# Bipolar_Stepper_Motor_Controller_RevA.net
KiCad netlist of a schematic drawn in EAGLE
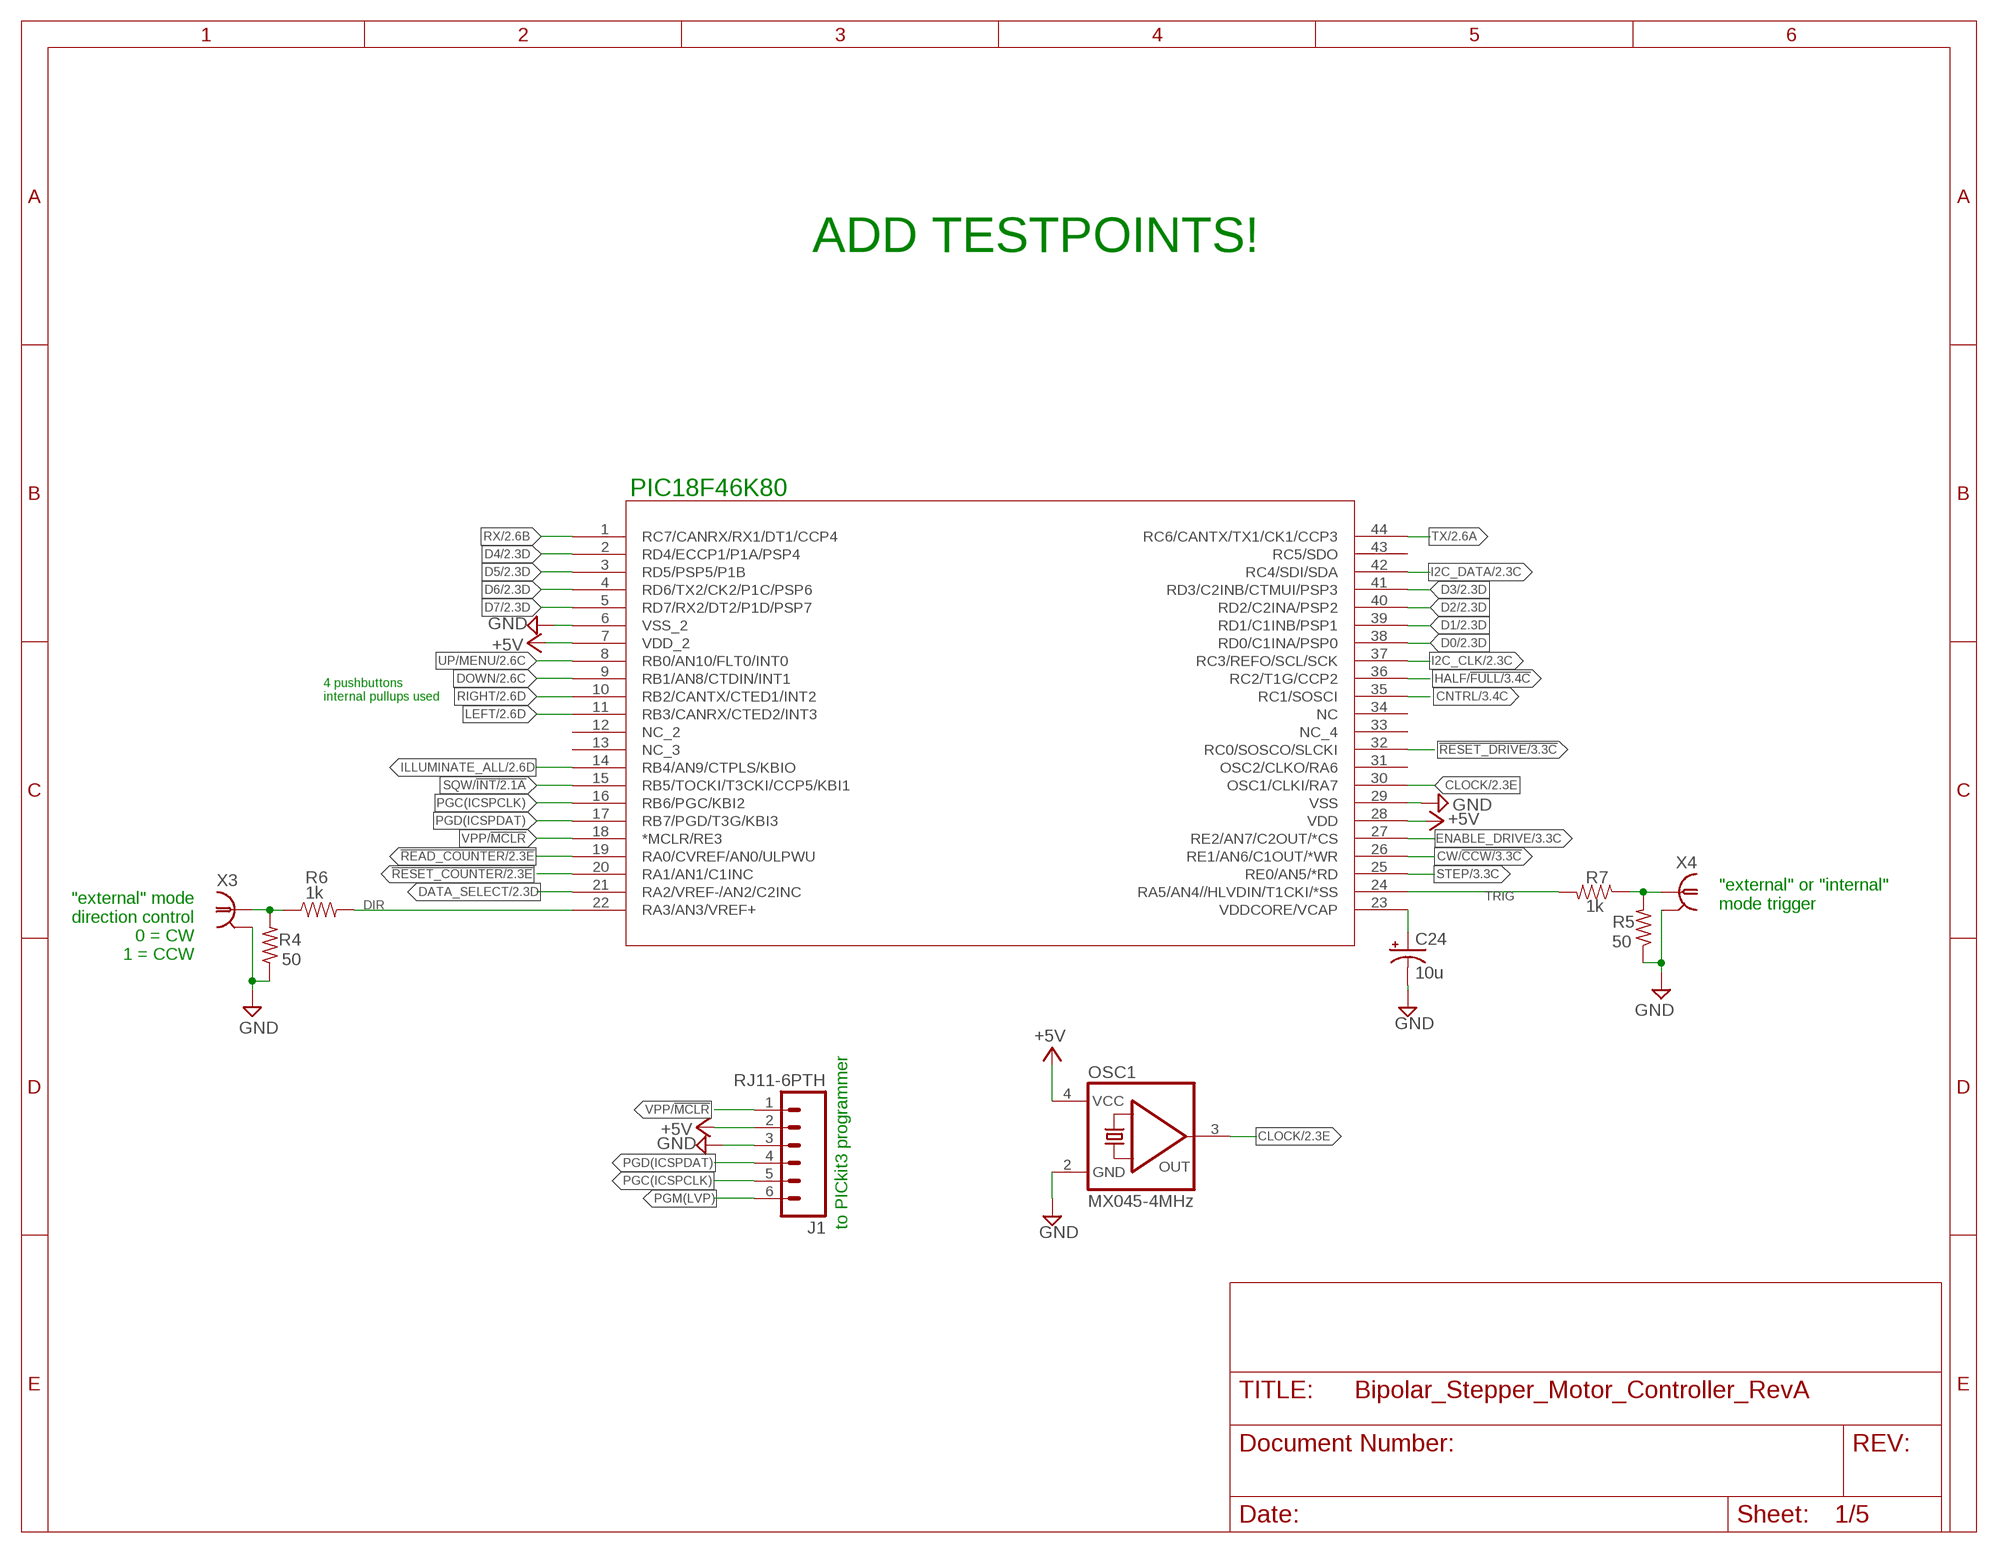
[diagram p0: schematic, sheet 1]
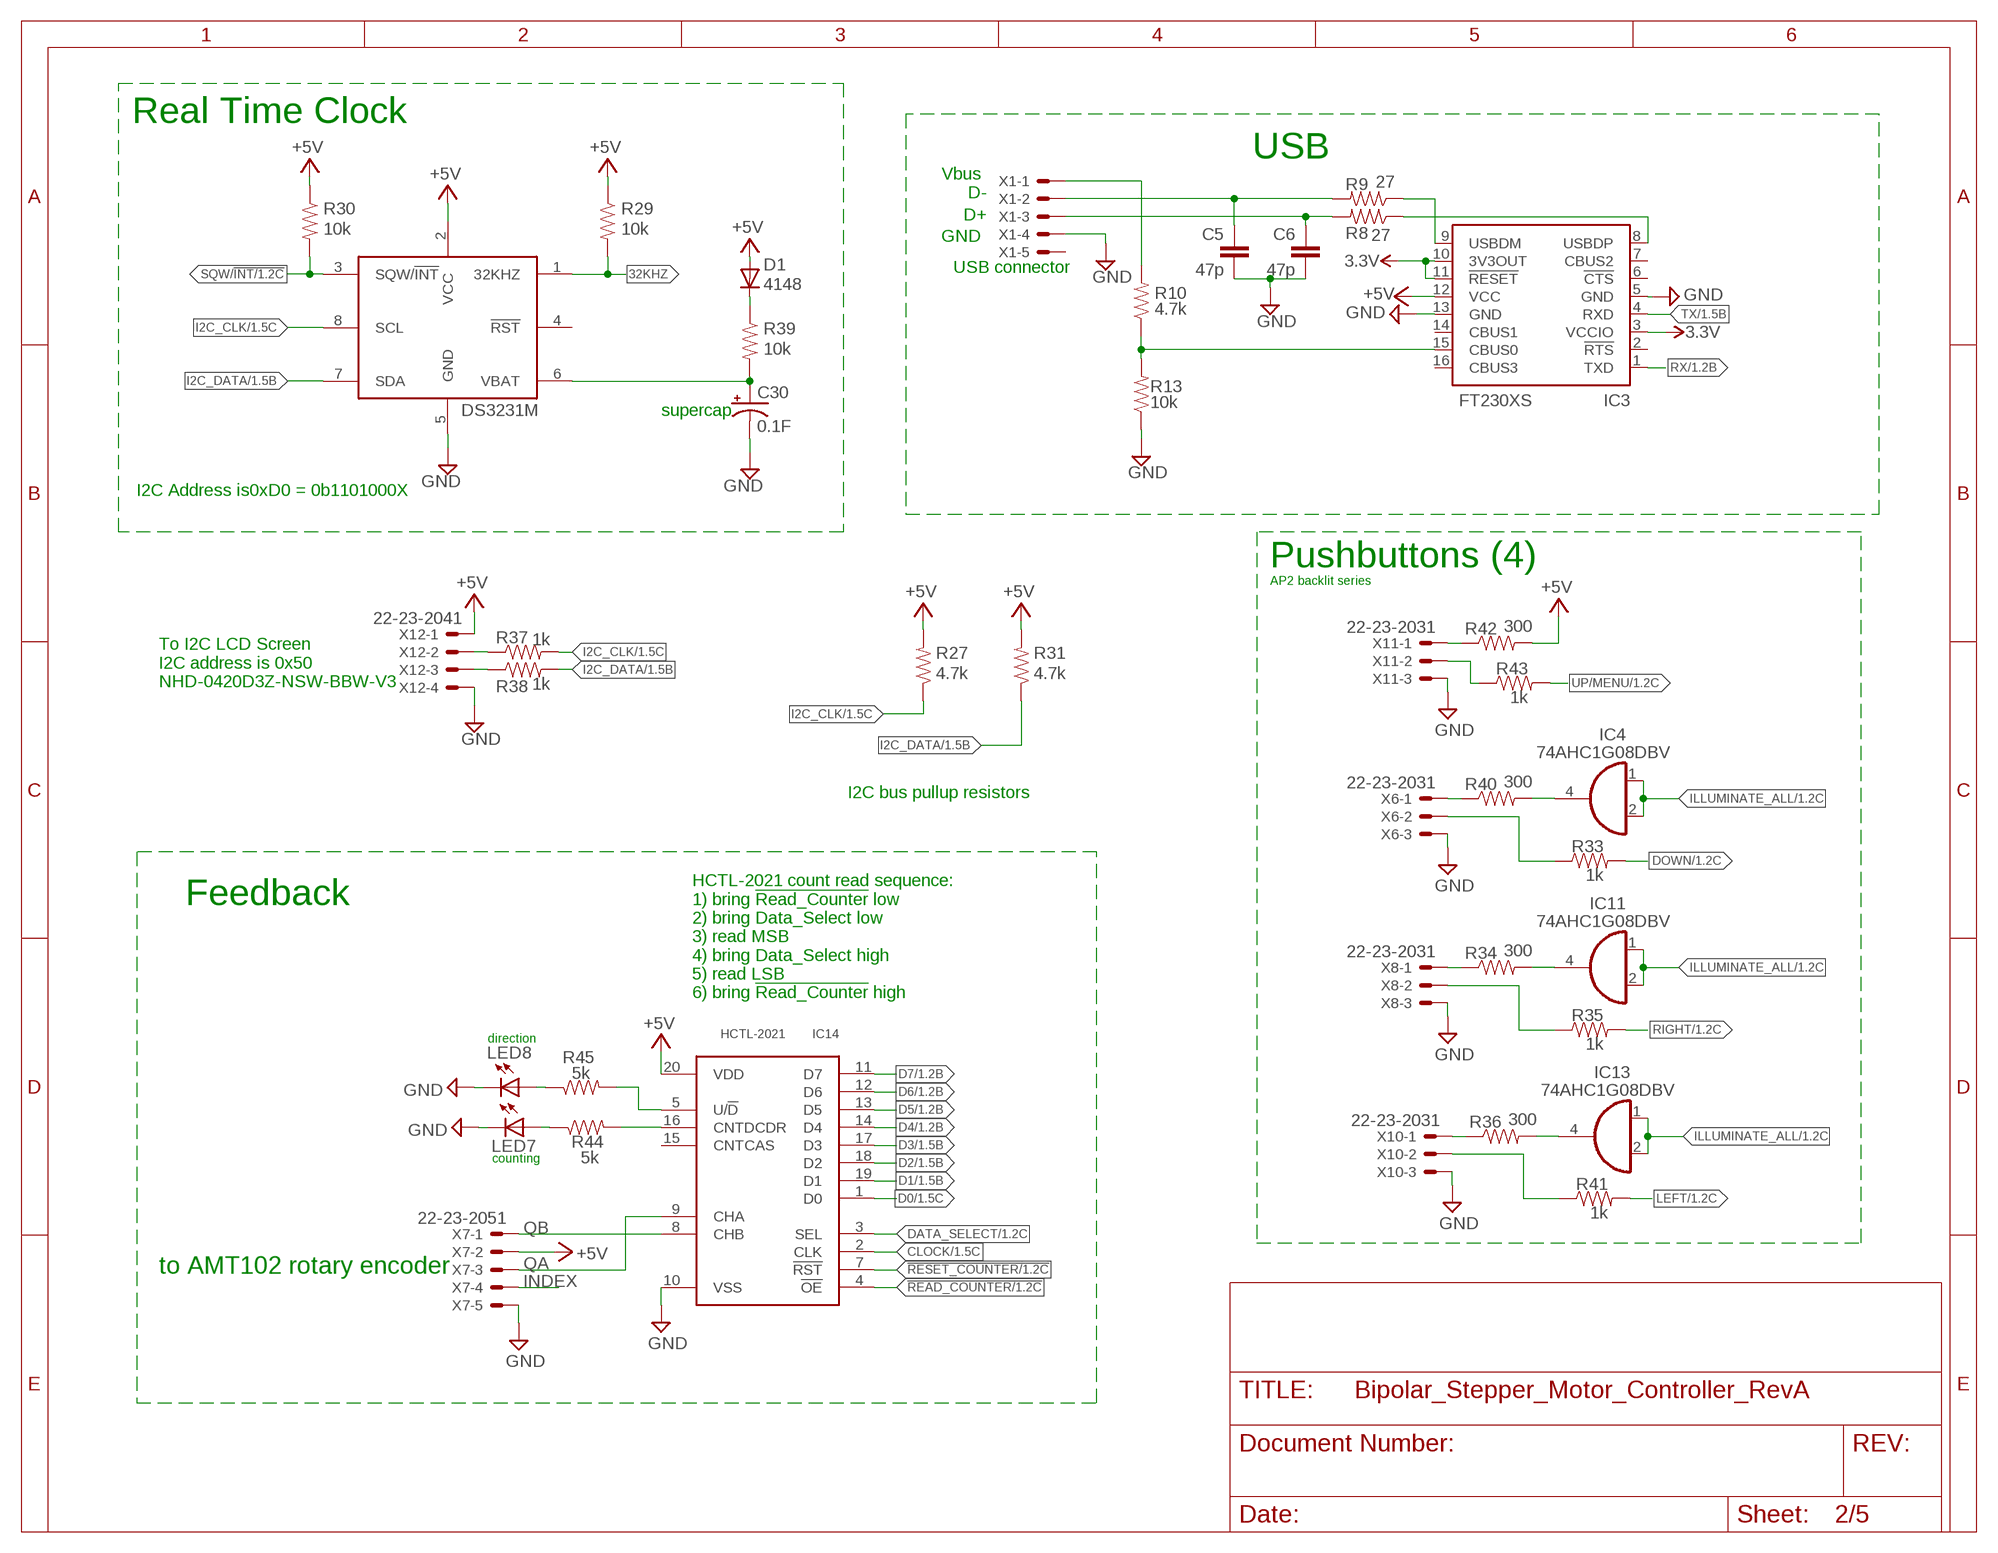
[diagram p1: schematic, sheet 2]
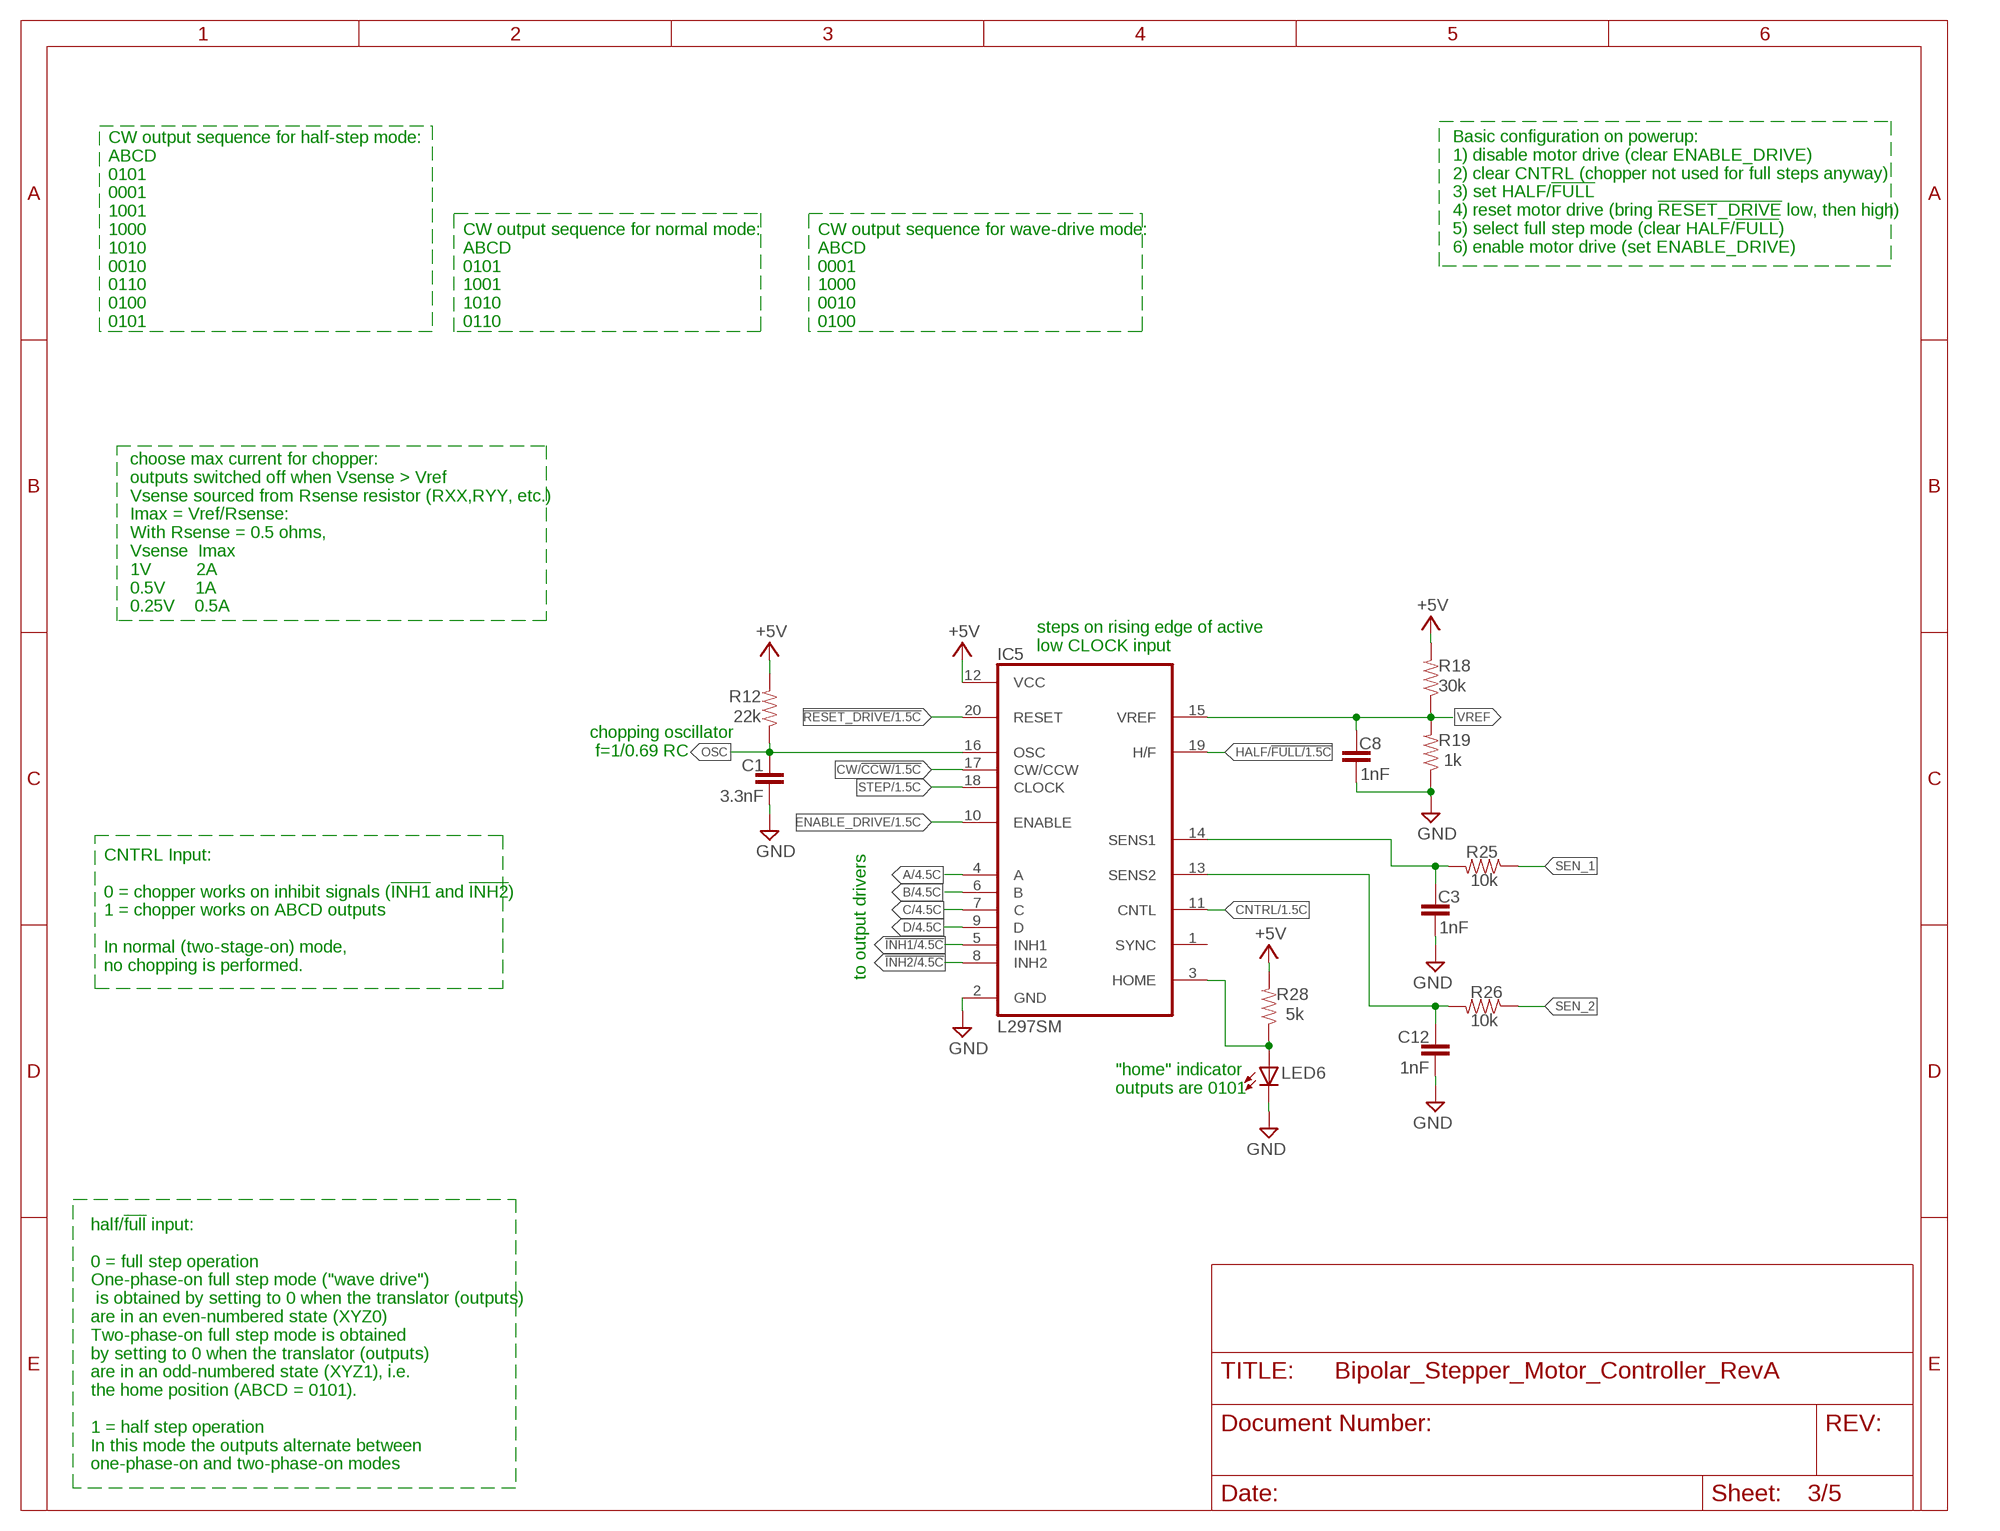
[diagram p2: schematic, sheet 3]
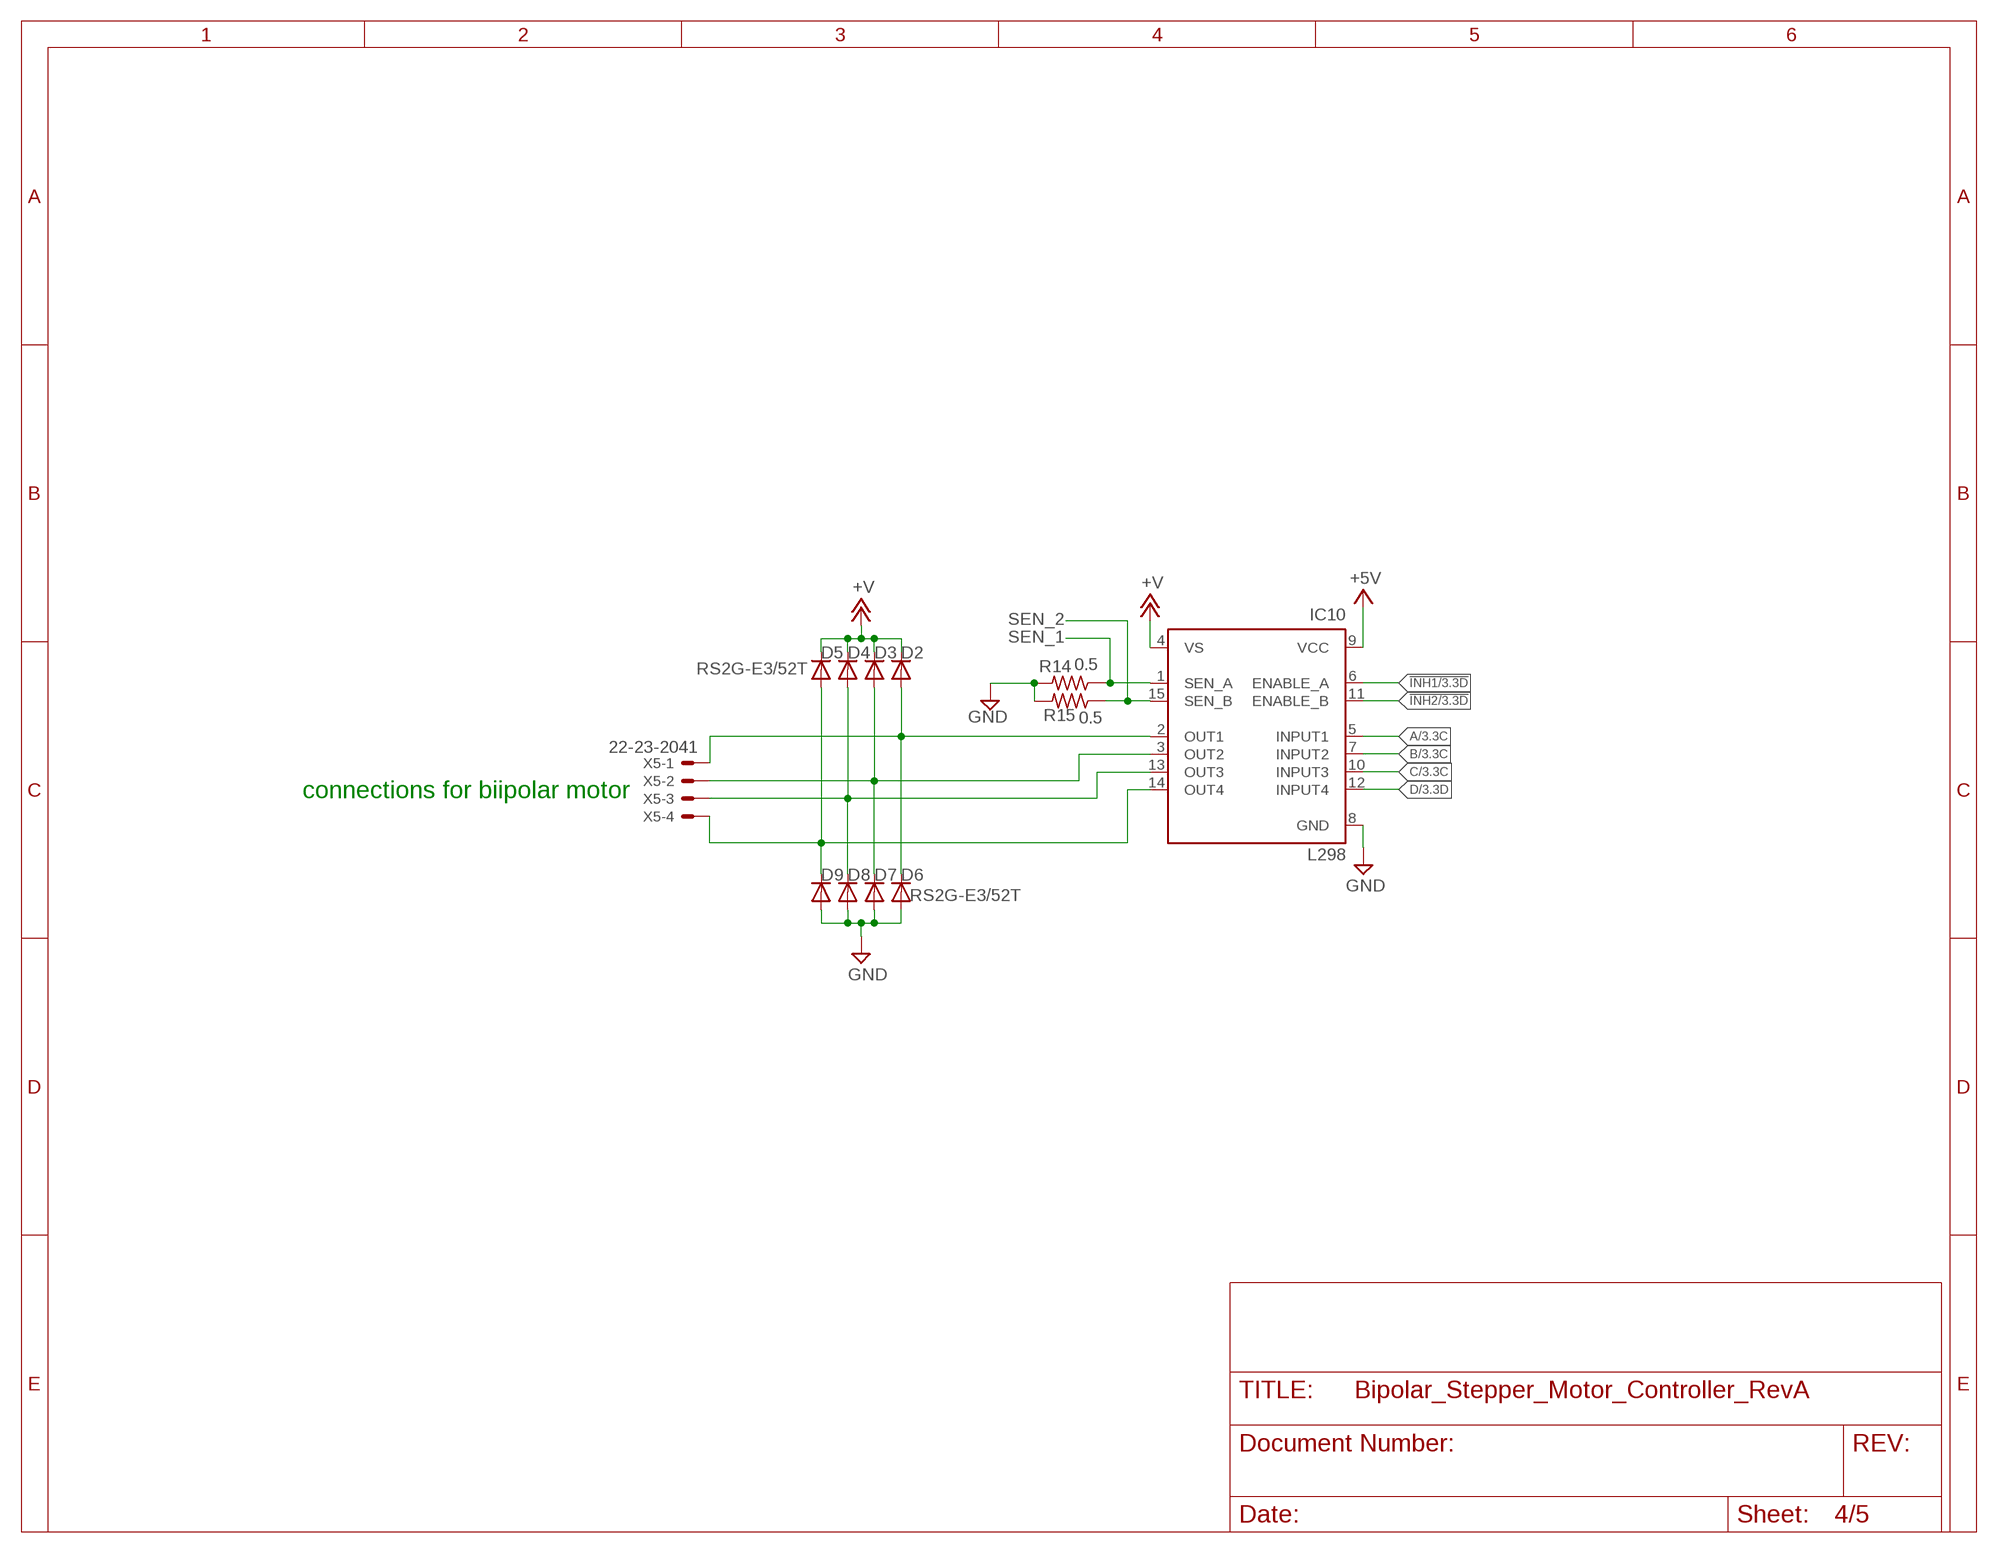
[diagram p3: schematic, sheet 4]
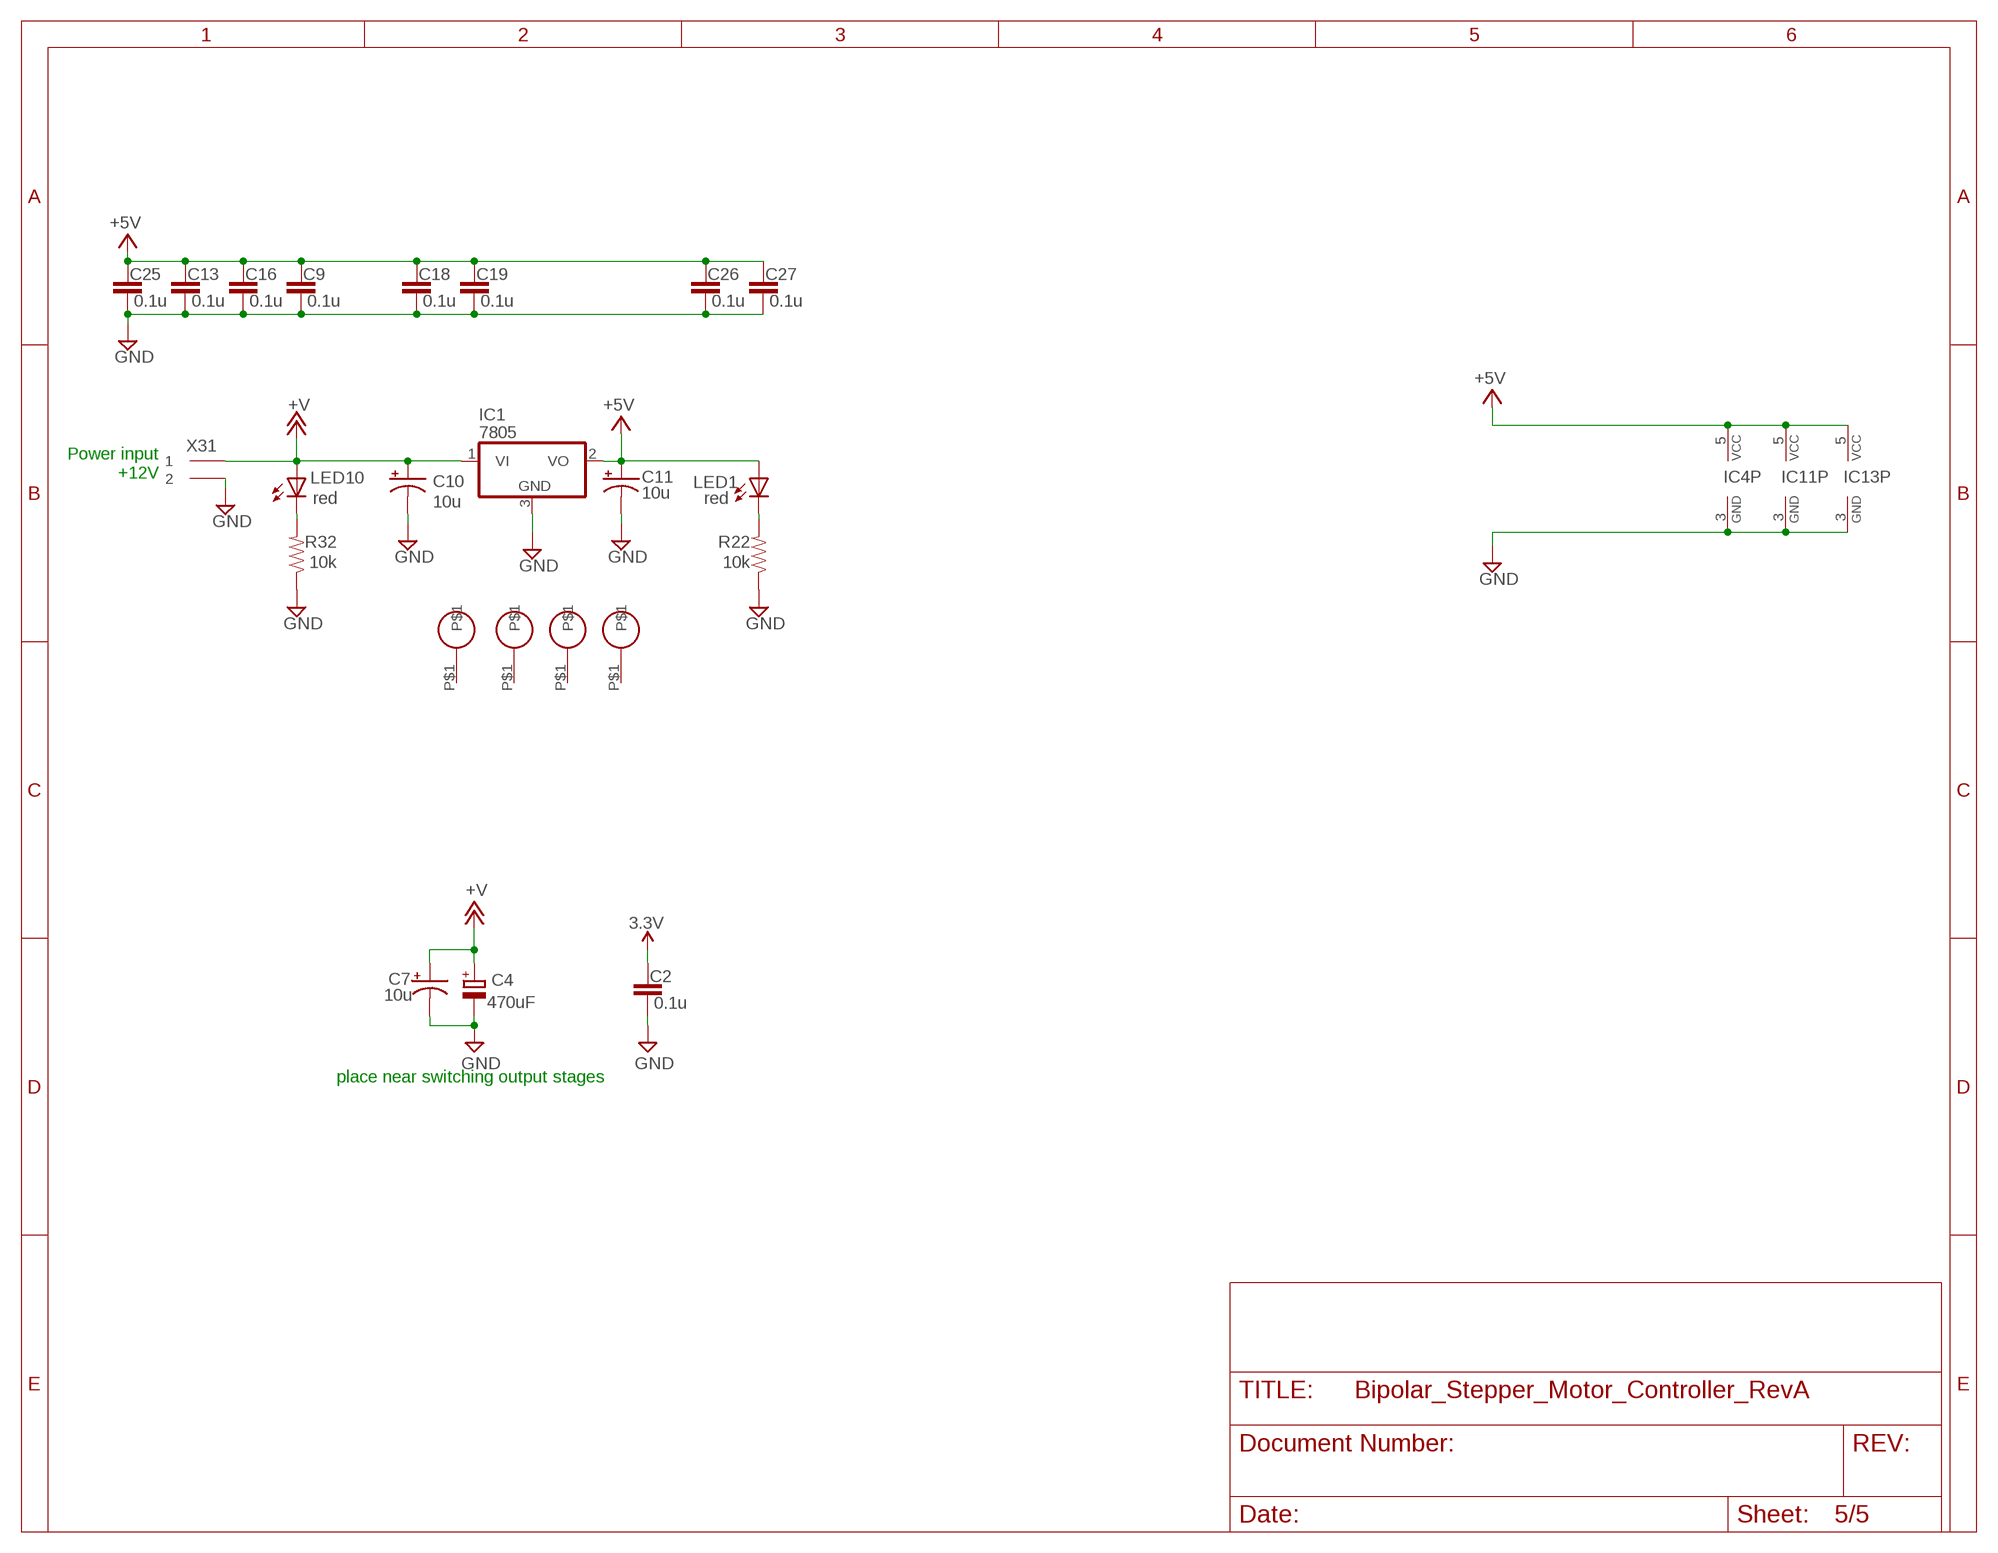
[diagram p4: schematic, sheet 5]

(export (version "E")
  (design (tool "Eeschema 10.0.6"))
  (components
    (comp (ref "C24")
      (value "10u")
      (footprint "eagle-import:EIA3216")
      (libsource (lib "eagle-import") (part "CAP_POL1206"))
    )
    (comp (ref "IC12")
      (value "PIC18F46K80")
      (footprint "eagle-import:TQFP44_MC")
      (libsource (lib "eagle-import") (part "PIC18F46K80"))
    )
    (comp (ref "J1")
      (value "RJ11-6PTH")
      (footprint "eagle-import:RJ11-6")
      (libsource (lib "eagle-import") (part "RJ11-6PTH"))
    )
    (comp (ref "OSC1")
      (value "MX045-4MHz")
      (footprint "eagle-import:DIL08-4")
      (libsource (lib "eagle-import") (part "SG531"))
    )
    (comp (ref "R4")
      (value "50")
      (footprint "eagle-import:R2512")
      (libsource (lib "eagle-import") (part "R-US_R2512"))
    )
    (comp (ref "R5")
      (value "50")
      (footprint "eagle-import:R2512")
      (libsource (lib "eagle-import") (part "R-US_R2512"))
    )
    (comp (ref "R6")
      (value "1k")
      (footprint "eagle-import:0805")
      (libsource (lib "eagle-import") (part "RESISTOR"))
    )
    (comp (ref "R7")
      (value "1k")
      (footprint "eagle-import:0805")
      (libsource (lib "eagle-import") (part "RESISTOR"))
    )
    (comp (ref "X3")
      (value "1-227161-0")
      (footprint "eagle-import:AMP_227161")
      (fields (field (name "MF") "TYCO ELECTRONICS") (field (name "MPN") "1-227161"))
      (libsource (lib "eagle-import") (part "?2271611--0"))
    )
    (comp (ref "X4")
      (value "1-227161-0")
      (footprint "eagle-import:AMP_227161")
      (fields (field (name "MF") "TYCO ELECTRONICS") (field (name "MPN") "1-227161"))
      (libsource (lib "eagle-import") (part "?2271611--0"))
    )
    (comp (ref "D2")
      (value "RS2G-E3/52T")
      (footprint "eagle-import:DO214AA")
      (libsource (lib "eagle-import") (part "DIODE-DO214AA"))
    )
    (comp (ref "D3")
      (value "RS2G-E3/52T")
      (footprint "eagle-import:DO214AA")
      (libsource (lib "eagle-import") (part "DIODE-DO214AA"))
    )
    (comp (ref "D4")
      (value "RS2G-E3/52T")
      (footprint "eagle-import:DO214AA")
      (libsource (lib "eagle-import") (part "DIODE-DO214AA"))
    )
    (comp (ref "D5")
      (value "RS2G-E3/52T")
      (footprint "eagle-import:DO214AA")
      (libsource (lib "eagle-import") (part "DIODE-DO214AA"))
    )
    (comp (ref "D6")
      (value "RS2G-E3/52T")
      (footprint "eagle-import:DO214AA")
      (libsource (lib "eagle-import") (part "DIODE-DO214AA"))
    )
    (comp (ref "D7")
      (value "RS2G-E3/52T")
      (footprint "eagle-import:DO214AA")
      (libsource (lib "eagle-import") (part "DIODE-DO214AA"))
    )
    (comp (ref "D8")
      (value "RS2G-E3/52T")
      (footprint "eagle-import:DO214AA")
      (libsource (lib "eagle-import") (part "DIODE-DO214AA"))
    )
    (comp (ref "D9")
      (value "RS2G-E3/52T")
      (footprint "eagle-import:DO214AA")
      (libsource (lib "eagle-import") (part "DIODE-DO214AA"))
    )
    (comp (ref "IC10")
      (value "L298")
      (footprint "eagle-import:MULTIWATT-15")
      (fields (field (name "MPN") "L298N"))
      (libsource (lib "eagle-import") (part "L298"))
    )
    (comp (ref "R14")
      (value "0.5")
      (footprint "eagle-import:R2512")
      (libsource (lib "eagle-import") (part "resistor_R-US_R2512"))
    )
    (comp (ref "R15")
      (value "0.5")
      (footprint "eagle-import:R2512")
      (libsource (lib "eagle-import") (part "resistor_R-US_R2512"))
    )
    (comp (ref "X5")
      (value "22-23-2041")
      (footprint "eagle-import:22-23-2041")
      (fields (field (name "MF") "MOLEX"))
      (libsource (lib "eagle-import") (part "22-23-2041"))
    )
    (comp (ref "C1")
      (value "3.3nF")
      (footprint "eagle-import:0603-CAP")
      (libsource (lib "eagle-import") (part "CAP0603-CAP"))
    )
    (comp (ref "C3")
      (value "1nF")
      (footprint "eagle-import:0603-CAP")
      (libsource (lib "eagle-import") (part "CAP0603-CAP"))
    )
    (comp (ref "C8")
      (value "1nF")
      (footprint "eagle-import:0603-CAP")
      (libsource (lib "eagle-import") (part "CAP0603-CAP"))
    )
    (comp (ref "C12")
      (value "1nF")
      (footprint "eagle-import:0603-CAP")
      (libsource (lib "eagle-import") (part "CAP0603-CAP"))
    )
    (comp (ref "IC5")
      (value "L297SM")
      (footprint "eagle-import:SO20")
      (libsource (lib "eagle-import") (part "L297SM"))
    )
    (comp (ref "LED6")
      (value "red")
      (footprint "eagle-import:CHIPLED_0603")
      (libsource (lib "eagle-import") (part "LEDCHIPLED_0603"))
    )
    (comp (ref "R12")
      (value "22k")
      (footprint "eagle-import:0603-RES")
      (libsource (lib "eagle-import") (part "RESISTOR0603-RES"))
    )
    (comp (ref "R18")
      (value "30k")
      (footprint "eagle-import:0603-RES")
      (libsource (lib "eagle-import") (part "RESISTOR0603-RES"))
    )
    (comp (ref "R19")
      (value "1k")
      (footprint "eagle-import:0603-RES")
      (libsource (lib "eagle-import") (part "RESISTOR0603-RES"))
    )
    (comp (ref "R25")
      (value "10k")
      (footprint "eagle-import:0603-RES")
      (libsource (lib "eagle-import") (part "RESISTOR0603-RES"))
    )
    (comp (ref "R26")
      (value "10k")
      (footprint "eagle-import:0603-RES")
      (libsource (lib "eagle-import") (part "RESISTOR0603-RES"))
    )
    (comp (ref "R28")
      (value "5k")
      (footprint "eagle-import:0603-RES")
      (libsource (lib "eagle-import") (part "RESISTOR0603-RES"))
    )
    (comp (ref "C5")
      (value "47p")
      (footprint "eagle-import:0805")
      (libsource (lib "eagle-import") (part "CAP0805"))
    )
    (comp (ref "C6")
      (value "47p")
      (footprint "eagle-import:0805")
      (libsource (lib "eagle-import") (part "CAP0805"))
    )
    (comp (ref "C30")
      (value "0.1F")
      (footprint "eagle-import:P128-60")
      (libsource (lib "eagle-import") (part "CPOL-USP128-60"))
    )
    (comp (ref "D1")
      (value "4148")
      (footprint "eagle-import:SOT23-3")
      (libsource (lib "eagle-import") (part "DIODESOT23"))
    )
    (comp (ref "IC3")
      (value "FT230XS")
      (footprint "eagle-import:SSOP16")
      (libsource (lib "eagle-import") (part "FT230XS"))
    )
    (comp (ref "IC4")
      (value "74AHC1G08DBV")
      (footprint "eagle-import:SOT23-5")
      (libsource (lib "eagle-import") (part "741G08DBVAHC"))
    )
    (comp (ref "IC6")
      (value "DS3231M")
      (footprint "eagle-import:8-SOIC")
      (libsource (lib "eagle-import") (part "DS3231M"))
    )
    (comp (ref "IC11")
      (value "74AHC1G08DBV")
      (footprint "eagle-import:SOT23-5")
      (libsource (lib "eagle-import") (part "741G08DBVAHC"))
    )
    (comp (ref "IC13")
      (value "74AHC1G08DBV")
      (footprint "eagle-import:SOT23-5")
      (libsource (lib "eagle-import") (part "741G08DBVAHC"))
    )
    (comp (ref "IC14")
      (value "HCTL-2021")
      (footprint "eagle-import:PLCC20")
      (libsource (lib "eagle-import") (part "HCTL-2021"))
    )
    (comp (ref "LED7")
      (value "red")
      (footprint "eagle-import:CHIPLED_0603")
      (libsource (lib "eagle-import") (part "LEDCHIPLED_0603"))
    )
    (comp (ref "LED8")
      (value "red")
      (footprint "eagle-import:CHIPLED_0603")
      (libsource (lib "eagle-import") (part "LEDCHIPLED_0603"))
    )
    (comp (ref "R8")
      (value "27")
      (footprint "eagle-import:0805")
      (libsource (lib "eagle-import") (part "RESISTOR"))
    )
    (comp (ref "R9")
      (value "27")
      (footprint "eagle-import:0805")
      (libsource (lib "eagle-import") (part "RESISTOR"))
    )
    (comp (ref "R10")
      (value "4.7k")
      (footprint "eagle-import:0805")
      (libsource (lib "eagle-import") (part "RESISTOR"))
    )
    (comp (ref "R13")
      (value "10k")
      (footprint "eagle-import:0805")
      (libsource (lib "eagle-import") (part "RESISTOR"))
    )
    (comp (ref "R27")
      (value "4.7k")
      (footprint "eagle-import:0603-RES")
      (libsource (lib "eagle-import") (part "RESISTOR0603-RES"))
    )
    (comp (ref "R29")
      (value "10k")
      (footprint "eagle-import:0603-RES")
      (libsource (lib "eagle-import") (part "RESISTOR0603-RES"))
    )
    (comp (ref "R30")
      (value "10k")
      (footprint "eagle-import:0603-RES")
      (libsource (lib "eagle-import") (part "RESISTOR0603-RES"))
    )
    (comp (ref "R31")
      (value "4.7k")
      (footprint "eagle-import:0603-RES")
      (libsource (lib "eagle-import") (part "RESISTOR0603-RES"))
    )
    (comp (ref "R33")
      (value "1k")
      (footprint "eagle-import:0805")
      (libsource (lib "eagle-import") (part "RESISTOR"))
    )
    (comp (ref "R34")
      (value "300")
      (footprint "eagle-import:0805")
      (libsource (lib "eagle-import") (part "RESISTOR"))
    )
    (comp (ref "R35")
      (value "1k")
      (footprint "eagle-import:0805")
      (libsource (lib "eagle-import") (part "RESISTOR"))
    )
    (comp (ref "R36")
      (value "300")
      (footprint "eagle-import:0805")
      (libsource (lib "eagle-import") (part "RESISTOR"))
    )
    (comp (ref "R37")
      (value "1k")
      (footprint "eagle-import:0805")
      (libsource (lib "eagle-import") (part "RESISTOR"))
    )
    (comp (ref "R38")
      (value "1k")
      (footprint "eagle-import:0805")
      (libsource (lib "eagle-import") (part "RESISTOR"))
    )
    (comp (ref "R39")
      (value "10k")
      (footprint "eagle-import:0603-RES")
      (libsource (lib "eagle-import") (part "RESISTOR0603-RES"))
    )
    (comp (ref "R40")
      (value "300")
      (footprint "eagle-import:0805")
      (libsource (lib "eagle-import") (part "RESISTOR"))
    )
    (comp (ref "R41")
      (value "1k")
      (footprint "eagle-import:0805")
      (libsource (lib "eagle-import") (part "RESISTOR"))
    )
    (comp (ref "R42")
      (value "300")
      (footprint "eagle-import:0805")
      (libsource (lib "eagle-import") (part "RESISTOR"))
    )
    (comp (ref "R43")
      (value "1k")
      (footprint "eagle-import:0805")
      (libsource (lib "eagle-import") (part "RESISTOR"))
    )
    (comp (ref "R44")
      (value "5k")
      (footprint "eagle-import:0603-RES")
      (libsource (lib "eagle-import") (part "RESISTOR0603-RES"))
    )
    (comp (ref "R45")
      (value "5k")
      (footprint "eagle-import:0603-RES")
      (libsource (lib "eagle-import") (part "RESISTOR0603-RES"))
    )
    (comp (ref "X1")
      (value "22-23-2051")
      (footprint "eagle-import:22-23-2051")
      (fields (field (name "MF") "MOLEX"))
      (libsource (lib "eagle-import") (part "22-23-2051"))
    )
    (comp (ref "X6")
      (value "22-23-2031")
      (footprint "eagle-import:22-23-2031")
      (fields (field (name "MF") "MOLEX"))
      (libsource (lib "eagle-import") (part "22-23-2031"))
    )
    (comp (ref "X7")
      (value "22-23-2051")
      (footprint "eagle-import:22-23-2051")
      (fields (field (name "MF") "MOLEX"))
      (libsource (lib "eagle-import") (part "22-23-2051"))
    )
    (comp (ref "X8")
      (value "22-23-2031")
      (footprint "eagle-import:22-23-2031")
      (fields (field (name "MF") "MOLEX"))
      (libsource (lib "eagle-import") (part "22-23-2031"))
    )
    (comp (ref "X10")
      (value "22-23-2031")
      (footprint "eagle-import:22-23-2031")
      (fields (field (name "MF") "MOLEX"))
      (libsource (lib "eagle-import") (part "22-23-2031"))
    )
    (comp (ref "X11")
      (value "22-23-2031")
      (footprint "eagle-import:22-23-2031")
      (fields (field (name "MF") "MOLEX"))
      (libsource (lib "eagle-import") (part "22-23-2031"))
    )
    (comp (ref "X12")
      (value "22-23-2041")
      (footprint "eagle-import:22-23-2041")
      (fields (field (name "MF") "MOLEX"))
      (libsource (lib "eagle-import") (part "22-23-2041"))
    )
    (comp (ref "C2")
      (value "0.1u")
      (footprint "eagle-import:0603-CAP")
      (libsource (lib "eagle-import") (part "CAP0603-CAP"))
    )
    (comp (ref "C4")
      (value "470uF")
      (footprint "eagle-import:SANYO-OSCON_SMD_F8")
      (libsource (lib "eagle-import") (part "CPOL-EUSANYO_SMD_F8"))
    )
    (comp (ref "C7")
      (value "10u")
      (footprint "eagle-import:EIA3216")
      (libsource (lib "eagle-import") (part "CAP_POL1206"))
    )
    (comp (ref "C9")
      (value "0.1u")
      (footprint "eagle-import:0603-CAP")
      (libsource (lib "eagle-import") (part "CAP0603-CAP"))
    )
    (comp (ref "C10")
      (value "10u")
      (footprint "eagle-import:EIA3216")
      (libsource (lib "eagle-import") (part "CAP_POL1206"))
    )
    (comp (ref "C11")
      (value "10u")
      (footprint "eagle-import:EIA3216")
      (libsource (lib "eagle-import") (part "CAP_POL1206"))
    )
    (comp (ref "C13")
      (value "0.1u")
      (footprint "eagle-import:0603-CAP")
      (libsource (lib "eagle-import") (part "CAP0603-CAP"))
    )
    (comp (ref "C16")
      (value "0.1u")
      (footprint "eagle-import:0603-CAP")
      (libsource (lib "eagle-import") (part "CAP0603-CAP"))
    )
    (comp (ref "C18")
      (value "0.1u")
      (footprint "eagle-import:0603-CAP")
      (libsource (lib "eagle-import") (part "CAP0603-CAP"))
    )
    (comp (ref "C19")
      (value "0.1u")
      (footprint "eagle-import:0603-CAP")
      (libsource (lib "eagle-import") (part "CAP0603-CAP"))
    )
    (comp (ref "C25")
      (value "0.1u")
      (footprint "eagle-import:0603-CAP")
      (libsource (lib "eagle-import") (part "CAP0603-CAP"))
    )
    (comp (ref "C26")
      (value "0.1u")
      (footprint "eagle-import:0603-CAP")
      (libsource (lib "eagle-import") (part "CAP0603-CAP"))
    )
    (comp (ref "C27")
      (value "0.1u")
      (footprint "eagle-import:0603-CAP")
      (libsource (lib "eagle-import") (part "CAP0603-CAP"))
    )
    (comp (ref "IC1")
      (value "7805")
      (footprint "eagle-import:TO252")
      (libsource (lib "eagle-import") (part "78DT24"))
    )
    (comp (ref "LED1")
      (value "red")
      (footprint "eagle-import:CHIPLED_0805")
      (libsource (lib "eagle-import") (part "LEDCHIPLED_0805"))
    )
    (comp (ref "LED10")
      (value "red")
      (footprint "eagle-import:CHIPLED_0805")
      (libsource (lib "eagle-import") (part "LEDCHIPLED_0805"))
    )
    (comp (ref "R22")
      (value "10k")
      (footprint "eagle-import:0805")
      (libsource (lib "eagle-import") (part "RESISTOR"))
    )
    (comp (ref "R32")
      (value "10k")
      (footprint "eagle-import:0805")
      (libsource (lib "eagle-import") (part "RESISTOR"))
    )
    (comp (ref "U$1")
      (value "2-56")
      (footprint "eagle-import:2-56")
      (libsource (lib "eagle-import") (part "2-56"))
    )
    (comp (ref "U$2")
      (value "2-56")
      (footprint "eagle-import:2-56")
      (libsource (lib "eagle-import") (part "2-56"))
    )
    (comp (ref "U$3")
      (value "2-56")
      (footprint "eagle-import:2-56")
      (libsource (lib "eagle-import") (part "2-56"))
    )
    (comp (ref "U$4")
      (value "2-56")
      (footprint "eagle-import:2-56")
      (libsource (lib "eagle-import") (part "2-56"))
    )
    (comp (ref "X31")
      (value "SL_70543_2")
      (footprint "eagle-import:SL_70543_2")
      (libsource (lib "eagle-import") (part "SL_70543_2"))
    )
  )
  (nets
    (net (code "1") (name "+5V") (class "Default")
      (node (ref "C11") (pin "A") (pinfunction "+_A") (pintype "passive"))
      (node (ref "C13") (pin "1") (pinfunction "1_1") (pintype "passive"))
      (node (ref "C16") (pin "1") (pinfunction "1_1") (pintype "passive"))
      (node (ref "C18") (pin "1") (pinfunction "1_1") (pintype "passive"))
      (node (ref "C19") (pin "1") (pinfunction "1_1") (pintype "passive"))
      (node (ref "C25") (pin "1") (pinfunction "1_1") (pintype "passive"))
      (node (ref "C26") (pin "1") (pinfunction "1_1") (pintype "passive"))
      (node (ref "C27") (pin "1") (pinfunction "1_1") (pintype "passive"))
      (node (ref "C9") (pin "1") (pinfunction "1_1") (pintype "passive"))
      (node (ref "D1") (pin "1") (pinfunction "A_1") (pintype "passive"))
      (node (ref "IC1") (pin "2") (pinfunction "VO_2") (pintype "passive"))
      (node (ref "IC10") (pin "9") (pinfunction "VCC_9") (pintype "power_in"))
      (node (ref "IC11") (pin "5") (pinfunction "VCC_5") (pintype "power_in"))
      (node (ref "IC12") (pin "28") (pinfunction "VDD_28") (pintype "passive"))
      (node (ref "IC12") (pin "7") (pinfunction "VDD_2_7") (pintype "passive"))
      (node (ref "IC13") (pin "5") (pinfunction "VCC_5") (pintype "power_in"))
      (node (ref "IC14") (pin "20") (pinfunction "VDD_20") (pintype "bidirectional"))
      (node (ref "IC3") (pin "12") (pinfunction "VCC_12") (pintype "power_in"))
      (node (ref "IC4") (pin "5") (pinfunction "VCC_5") (pintype "power_in"))
      (node (ref "IC5") (pin "12") (pinfunction "VCC_12") (pintype "power_in"))
      (node (ref "IC6") (pin "2") (pinfunction "VCC_2") (pintype "bidirectional"))
      (node (ref "J1") (pin "2") (pinfunction "2_2") (pintype "passive"))
      (node (ref "LED1") (pin "A") (pinfunction "A_A") (pintype "passive"))
      (node (ref "OSC1") (pin "4") (pinfunction "VCC_4") (pintype "power_in"))
      (node (ref "R12") (pin "2") (pinfunction "2_2") (pintype "passive"))
      (node (ref "R18") (pin "2") (pinfunction "2_2") (pintype "passive"))
      (node (ref "R27") (pin "2") (pinfunction "2_2") (pintype "passive"))
      (node (ref "R28") (pin "2") (pinfunction "2_2") (pintype "passive"))
      (node (ref "R29") (pin "1") (pinfunction "1_1") (pintype "passive"))
      (node (ref "R30") (pin "1") (pinfunction "1_1") (pintype "passive"))
      (node (ref "R31") (pin "2") (pinfunction "2_2") (pintype "passive"))
      (node (ref "R42") (pin "2") (pinfunction "2_2") (pintype "passive"))
      (node (ref "X12") (pin "1") (pinfunction "S_1") (pintype "passive"))
      (node (ref "X7") (pin "2") (pinfunction "S_2") (pintype "passive"))
    )
    (net (code "2") (name "+V") (class "Default")
      (node (ref "C10") (pin "A") (pinfunction "+_A") (pintype "passive"))
      (node (ref "C4") (pin "+") (pinfunction "+_+") (pintype "passive"))
      (node (ref "C7") (pin "A") (pinfunction "+_A") (pintype "passive"))
      (node (ref "D2") (pin "C") (pinfunction "C_C") (pintype "passive"))
      (node (ref "D3") (pin "C") (pinfunction "C_C") (pintype "passive"))
      (node (ref "D4") (pin "C") (pinfunction "C_C") (pintype "passive"))
      (node (ref "D5") (pin "C") (pinfunction "C_C") (pintype "passive"))
      (node (ref "IC1") (pin "1") (pinfunction "VI_1") (pintype "input"))
      (node (ref "IC10") (pin "4") (pinfunction "VS_4") (pintype "power_in"))
      (node (ref "LED10") (pin "A") (pinfunction "A_A") (pintype "passive"))
      (node (ref "X31") (pin "P$1") (pinfunction "1_P$1") (pintype "bidirectional"))
    )
    (net (code "3") (name "3.3V") (class "Default")
      (node (ref "C2") (pin "1") (pinfunction "1_1") (pintype "passive"))
      (node (ref "IC3") (pin "10") (pinfunction "3V3OUT_10") (pintype "output"))
      (node (ref "IC3") (pin "11") (pinfunction "~{RESET}_11") (pintype "input"))
      (node (ref "IC3") (pin "3") (pinfunction "VCCIO_3") (pintype "power_in"))
    )
    (net (code "4") (name "32KHZ") (class "Default")
      (node (ref "IC6") (pin "1") (pinfunction "32KHZ_1") (pintype "bidirectional"))
      (node (ref "R29") (pin "2") (pinfunction "2_2") (pintype "passive"))
    )
    (net (code "5") (name "A") (class "Default")
      (node (ref "IC10") (pin "5") (pinfunction "INPUT1_5") (pintype "input"))
      (node (ref "IC5") (pin "4") (pinfunction "A_4") (pintype "output"))
    )
    (net (code "6") (name "B") (class "Default")
      (node (ref "IC10") (pin "7") (pinfunction "INPUT2_7") (pintype "input"))
      (node (ref "IC5") (pin "6") (pinfunction "B_6") (pintype "output"))
    )
    (net (code "7") (name "C") (class "Default")
      (node (ref "IC10") (pin "10") (pinfunction "INPUT3_10") (pintype "input"))
      (node (ref "IC5") (pin "7") (pinfunction "C_7") (pintype "output"))
    )
    (net (code "8") (name "CLOCK") (class "Default")
      (node (ref "IC12") (pin "30") (pinfunction "OSC1/CLKI/RA7_30") (pintype "passive"))
      (node (ref "IC14") (pin "2") (pinfunction "CLK_2") (pintype "bidirectional"))
      (node (ref "OSC1") (pin "3") (pinfunction "OUT_3") (pintype "output"))
    )
    (net (code "9") (name "CNTRL") (class "Default")
      (node (ref "IC12") (pin "35") (pinfunction "RC1/SOSCI_35") (pintype "passive"))
      (node (ref "IC5") (pin "11") (pinfunction "CNTL_11") (pintype "input"))
    )
    (net (code "10") (name "CW{slash}~{CCW}") (class "Default")
      (node (ref "IC12") (pin "26") (pinfunction "RE1/AN6/C1OUT/*WR_26") (pintype "passive"))
      (node (ref "IC5") (pin "17") (pinfunction "CW/CCW_17") (pintype "input"))
    )
    (net (code "11") (name "D") (class "Default")
      (node (ref "IC10") (pin "12") (pinfunction "INPUT4_12") (pintype "input"))
      (node (ref "IC5") (pin "9") (pinfunction "D_9") (pintype "output"))
    )
    (net (code "12") (name "D0") (class "Default")
      (node (ref "IC12") (pin "38") (pinfunction "RD0/C1INA/PSP0_38") (pintype "passive"))
      (node (ref "IC14") (pin "1") (pinfunction "D0_1") (pintype "bidirectional"))
    )
    (net (code "13") (name "D1") (class "Default")
      (node (ref "IC12") (pin "39") (pinfunction "RD1/C1INB/PSP1_39") (pintype "passive"))
      (node (ref "IC14") (pin "19") (pinfunction "D1_19") (pintype "bidirectional"))
    )
    (net (code "14") (name "D2") (class "Default")
      (node (ref "IC12") (pin "40") (pinfunction "RD2/C2INA/PSP2_40") (pintype "passive"))
      (node (ref "IC14") (pin "18") (pinfunction "D2_18") (pintype "bidirectional"))
    )
    (net (code "15") (name "D3") (class "Default")
      (node (ref "IC12") (pin "41") (pinfunction "RD3/C2INB/CTMUI/PSP3_41") (pintype "passive"))
      (node (ref "IC14") (pin "17") (pinfunction "D3_17") (pintype "bidirectional"))
    )
    (net (code "16") (name "D4") (class "Default")
      (node (ref "IC12") (pin "2") (pinfunction "RD4/ECCP1/P1A/PSP4_2") (pintype "passive"))
      (node (ref "IC14") (pin "14") (pinfunction "D4_14") (pintype "bidirectional"))
    )
    (net (code "17") (name "D5") (class "Default")
      (node (ref "IC12") (pin "3") (pinfunction "RD5/PSP5/P1B_3") (pintype "passive"))
      (node (ref "IC14") (pin "13") (pinfunction "D5_13") (pintype "bidirectional"))
    )
    (net (code "18") (name "D6") (class "Default")
      (node (ref "IC12") (pin "4") (pinfunction "RD6/TX2/CK2/P1C/PSP6_4") (pintype "passive"))
      (node (ref "IC14") (pin "12") (pinfunction "D6_12") (pintype "bidirectional"))
    )
    (net (code "19") (name "D7") (class "Default")
      (node (ref "IC12") (pin "5") (pinfunction "RD7/RX2/DT2/P1D/PSP7_5") (pintype "passive"))
      (node (ref "IC14") (pin "11") (pinfunction "D7_11") (pintype "bidirectional"))
    )
    (net (code "20") (name "DATA_SELECT") (class "Default")
      (node (ref "IC12") (pin "21") (pinfunction "RA2/VREF-/AN2/C2INC_21") (pintype "passive"))
      (node (ref "IC14") (pin "3") (pinfunction "SEL_3") (pintype "bidirectional"))
    )
    (net (code "21") (name "DIR") (class "Default")
      (node (ref "IC12") (pin "22") (pinfunction "RA3/AN3/VREF+_22") (pintype "passive"))
      (node (ref "R6") (pin "2") (pinfunction "2_2") (pintype "passive"))
    )
    (net (code "22") (name "DOWN") (class "Default")
      (node (ref "IC12") (pin "9") (pinfunction "RB1/AN8/CTDIN/INT1_9") (pintype "passive"))
      (node (ref "R33") (pin "2") (pinfunction "2_2") (pintype "passive"))
    )
    (net (code "23") (name "ENABLE_DRIVE") (class "Default")
      (node (ref "IC12") (pin "27") (pinfunction "RE2/AN7/C2OUT/*CS_27") (pintype "passive"))
      (node (ref "IC5") (pin "10") (pinfunction "ENABLE_10") (pintype "input"))
    )
    (net (code "24") (name "GND") (class "Default")
      (node (ref "C1") (pin "2") (pinfunction "2_2") (pintype "passive"))
      (node (ref "C10") (pin "C") (pinfunction "-_C") (pintype "passive"))
      (node (ref "C11") (pin "C") (pinfunction "-_C") (pintype "passive"))
      (node (ref "C12") (pin "2") (pinfunction "2_2") (pintype "passive"))
      (node (ref "C13") (pin "2") (pinfunction "2_2") (pintype "passive"))
      (node (ref "C16") (pin "2") (pinfunction "2_2") (pintype "passive"))
      (node (ref "C18") (pin "2") (pinfunction "2_2") (pintype "passive"))
      (node (ref "C19") (pin "2") (pinfunction "2_2") (pintype "passive"))
      (node (ref "C2") (pin "2") (pinfunction "2_2") (pintype "passive"))
      (node (ref "C24") (pin "C") (pinfunction "-_C") (pintype "passive"))
      (node (ref "C25") (pin "2") (pinfunction "2_2") (pintype "passive"))
      (node (ref "C26") (pin "2") (pinfunction "2_2") (pintype "passive"))
      (node (ref "C27") (pin "2") (pinfunction "2_2") (pintype "passive"))
      (node (ref "C3") (pin "2") (pinfunction "2_2") (pintype "passive"))
      (node (ref "C30") (pin "-") (pinfunction "-_-") (pintype "passive"))
      (node (ref "C4") (pin "-") (pinfunction "-_-") (pintype "passive"))
      (node (ref "C5") (pin "2") (pinfunction "2_2") (pintype "passive"))
      (node (ref "C6") (pin "2") (pinfunction "2_2") (pintype "passive"))
      (node (ref "C7") (pin "C") (pinfunction "-_C") (pintype "passive"))
      (node (ref "C8") (pin "2") (pinfunction "2_2") (pintype "passive"))
      (node (ref "C9") (pin "2") (pinfunction "2_2") (pintype "passive"))
      (node (ref "D6") (pin "A") (pinfunction "A_A") (pintype "passive"))
      (node (ref "D7") (pin "A") (pinfunction "A_A") (pintype "passive"))
      (node (ref "D8") (pin "A") (pinfunction "A_A") (pintype "passive"))
      (node (ref "D9") (pin "A") (pinfunction "A_A") (pintype "passive"))
      (node (ref "IC1") (pin "3") (pinfunction "GND_3") (pintype "passive"))
      (node (ref "IC10") (pin "8") (pinfunction "GND_8") (pintype "power_in"))
      (node (ref "IC11") (pin "3") (pinfunction "GND_3") (pintype "power_in"))
      (node (ref "IC12") (pin "29") (pinfunction "VSS_29") (pintype "passive"))
      (node (ref "IC12") (pin "6") (pinfunction "VSS_2_6") (pintype "passive"))
      (node (ref "IC13") (pin "3") (pinfunction "GND_3") (pintype "power_in"))
      (node (ref "IC14") (pin "10") (pinfunction "VSS_10") (pintype "bidirectional"))
      (node (ref "IC3") (pin "13") (pinfunction "GND_13") (pintype "power_in"))
      (node (ref "IC3") (pin "5") (pinfunction "GND_5") (pintype "power_in"))
      (node (ref "IC4") (pin "3") (pinfunction "GND_3") (pintype "power_in"))
      (node (ref "IC5") (pin "2") (pinfunction "GND_2") (pintype "power_in"))
      (node (ref "IC6") (pin "5") (pinfunction "GND_5") (pintype "bidirectional"))
      (node (ref "J1") (pin "3") (pinfunction "3_3") (pintype "passive"))
      (node (ref "LED6") (pin "C") (pinfunction "C_C") (pintype "passive"))
      (node (ref "LED7") (pin "C") (pinfunction "C_C") (pintype "passive"))
      (node (ref "LED8") (pin "C") (pinfunction "C_C") (pintype "passive"))
      (node (ref "OSC1") (pin "2") (pinfunction "GND_2") (pintype "power_in"))
      (node (ref "R13") (pin "1") (pinfunction "1_1") (pintype "passive"))
      (node (ref "R14") (pin "2") (pinfunction "2_2") (pintype "passive"))
      (node (ref "R15") (pin "2") (pinfunction "2_2") (pintype "passive"))
      (node (ref "R19") (pin "1") (pinfunction "1_1") (pintype "passive"))
      (node (ref "R22") (pin "1") (pinfunction "1_1") (pintype "passive"))
      (node (ref "R32") (pin "1") (pinfunction "1_1") (pintype "passive"))
      (node (ref "R4") (pin "1") (pinfunction "1_1") (pintype "passive"))
      (node (ref "R5") (pin "1") (pinfunction "1_1") (pintype "passive"))
      (node (ref "X1") (pin "4") (pinfunction "S_4") (pintype "passive"))
      (node (ref "X10") (pin "3") (pinfunction "S_3") (pintype "passive"))
      (node (ref "X11") (pin "3") (pinfunction "S_3") (pintype "passive"))
      (node (ref "X12") (pin "4") (pinfunction "S_4") (pintype "passive"))
      (node (ref "X3") (pin "2") (pinfunction "2_2") (pintype "passive"))
      (node (ref "X31") (pin "P$2") (pinfunction "2_P$2") (pintype "bidirectional"))
      (node (ref "X4") (pin "2") (pinfunction "2_2") (pintype "passive"))
      (node (ref "X6") (pin "3") (pinfunction "S_3") (pintype "passive"))
      (node (ref "X7") (pin "5") (pinfunction "S_5") (pintype "passive"))
      (node (ref "X8") (pin "3") (pinfunction "S_3") (pintype "passive"))
    )
    (net (code "25") (name "HALF{slash}~{FULL}") (class "Default")
      (node (ref "IC12") (pin "36") (pinfunction "RC2/T1G/CCP2_36") (pintype "passive"))
      (node (ref "IC5") (pin "19") (pinfunction "H/F_19") (pintype "input"))
    )
    (net (code "26") (name "I2C_CLK") (class "Default")
      (node (ref "IC12") (pin "37") (pinfunction "RC3/REFO/SCL/SCK_37") (pintype "passive"))
      (node (ref "IC6") (pin "8") (pinfunction "SCL_8") (pintype "bidirectional"))
      (node (ref "R27") (pin "1") (pinfunction "1_1") (pintype "passive"))
      (node (ref "R37") (pin "2") (pinfunction "2_2") (pintype "passive"))
    )
    (net (code "27") (name "I2C_DATA") (class "Default")
      (node (ref "IC12") (pin "42") (pinfunction "RC4/SDI/SDA_42") (pintype "passive"))
      (node (ref "IC6") (pin "7") (pinfunction "SDA_7") (pintype "bidirectional"))
      (node (ref "R31") (pin "1") (pinfunction "1_1") (pintype "passive"))
      (node (ref "R38") (pin "2") (pinfunction "2_2") (pintype "passive"))
    )
    (net (code "28") (name "ILLUMINATE_ALL") (class "Default")
      (node (ref "IC11") (pin "1") (pinfunction "I0_1") (pintype "input"))
      (node (ref "IC11") (pin "2") (pinfunction "I1_2") (pintype "input"))
      (node (ref "IC12") (pin "14") (pinfunction "RB4/AN9/CTPLS/KBIO_14") (pintype "passive"))
      (node (ref "IC13") (pin "1") (pinfunction "I0_1") (pintype "input"))
      (node (ref "IC13") (pin "2") (pinfunction "I1_2") (pintype "input"))
      (node (ref "IC4") (pin "1") (pinfunction "I0_1") (pintype "input"))
      (node (ref "IC4") (pin "2") (pinfunction "I1_2") (pintype "input"))
    )
    (net (code "29") (name "INDEX") (class "Default")
      (node (ref "X7") (pin "4") (pinfunction "S_4") (pintype "passive"))
    )
    (net (code "30") (name "LEFT") (class "Default")
      (node (ref "IC12") (pin "11") (pinfunction "RB3/CANRX/CTED2/INT3_11") (pintype "passive"))
      (node (ref "R41") (pin "2") (pinfunction "2_2") (pintype "passive"))
    )
    (net (code "31") (name "Net-(C24-+)") (class "Default")
      (node (ref "C24") (pin "A") (pinfunction "+_A") (pintype "passive"))
      (node (ref "IC12") (pin "23") (pinfunction "VDDCORE/VCAP_23") (pintype "passive"))
    )
    (net (code "32") (name "Net-(D1-C)") (class "Default")
      (node (ref "D1") (pin "3") (pinfunction "C_3") (pintype "passive"))
      (node (ref "R39") (pin "1") (pinfunction "1_1") (pintype "passive"))
    )
    (net (code "33") (name "Net-(IC3-CBUS0)") (class "Default")
      (node (ref "IC3") (pin "15") (pinfunction "CBUS0_15") (pintype "bidirectional"))
      (node (ref "R10") (pin "1") (pinfunction "1_1") (pintype "passive"))
      (node (ref "R13") (pin "2") (pinfunction "2_2") (pintype "passive"))
    )
    (net (code "34") (name "Net-(IC3-USBDM)") (class "Default")
      (node (ref "IC3") (pin "9") (pinfunction "USBDM_9") (pintype "input"))
      (node (ref "R9") (pin "1") (pinfunction "1_1") (pintype "passive"))
    )
    (net (code "35") (name "Net-(IC3-USBDP)") (class "Default")
      (node (ref "IC3") (pin "8") (pinfunction "USBDP_8") (pintype "input"))
      (node (ref "R8") (pin "1") (pinfunction "1_1") (pintype "passive"))
    )
    (net (code "36") (name "Net-(IC4A-O)") (class "Default")
      (node (ref "IC4") (pin "4") (pinfunction "O_4") (pintype "output"))
      (node (ref "R40") (pin "2") (pinfunction "2_2") (pintype "passive"))
    )
    (net (code "37") (name "Net-(IC5-HOME)") (class "Default")
      (node (ref "IC5") (pin "3") (pinfunction "HOME_3") (pintype "output"))
      (node (ref "LED6") (pin "A") (pinfunction "A_A") (pintype "passive"))
      (node (ref "R28") (pin "1") (pinfunction "1_1") (pintype "passive"))
    )
    (net (code "38") (name "Net-(IC5-SENS1)") (class "Default")
      (node (ref "C3") (pin "1") (pinfunction "1_1") (pintype "passive"))
      (node (ref "IC5") (pin "14") (pinfunction "SENS1_14") (pintype "output"))
      (node (ref "R25") (pin "2") (pinfunction "2_2") (pintype "passive"))
    )
    (net (code "39") (name "Net-(IC5-SENS2)") (class "Default")
      (node (ref "C12") (pin "1") (pinfunction "1_1") (pintype "passive"))
      (node (ref "IC5") (pin "13") (pinfunction "SENS2_13") (pintype "output"))
      (node (ref "R26") (pin "2") (pinfunction "2_2") (pintype "passive"))
    )
    (net (code "40") (name "Net-(IC6-VBAT)") (class "Default")
      (node (ref "C30") (pin "+") (pinfunction "+_+") (pintype "passive"))
      (node (ref "IC6") (pin "6") (pinfunction "VBAT_6") (pintype "bidirectional"))
      (node (ref "R39") (pin "2") (pinfunction "2_2") (pintype "passive"))
    )
    (net (code "41") (name "Net-(IC10-OUT1)") (class "Default")
      (node (ref "D2") (pin "A") (pinfunction "A_A") (pintype "passive"))
      (node (ref "D6") (pin "C") (pinfunction "C_C") (pintype "passive"))
      (node (ref "IC10") (pin "2") (pinfunction "OUT1_2") (pintype "output"))
      (node (ref "X5") (pin "1") (pinfunction "S_1") (pintype "passive"))
    )
    (net (code "42") (name "Net-(IC10-OUT2)") (class "Default")
      (node (ref "D3") (pin "A") (pinfunction "A_A") (pintype "passive"))
      (node (ref "D7") (pin "C") (pinfunction "C_C") (pintype "passive"))
      (node (ref "IC10") (pin "3") (pinfunction "OUT2_3") (pintype "output"))
      (node (ref "X5") (pin "2") (pinfunction "S_2") (pintype "passive"))
    )
    (net (code "43") (name "Net-(IC10-OUT3)") (class "Default")
      (node (ref "D4") (pin "A") (pinfunction "A_A") (pintype "passive"))
      (node (ref "D8") (pin "C") (pinfunction "C_C") (pintype "passive"))
      (node (ref "IC10") (pin "13") (pinfunction "OUT3_13") (pintype "output"))
      (node (ref "X5") (pin "3") (pinfunction "S_3") (pintype "passive"))
    )
    (net (code "44") (name "Net-(IC10-OUT4)") (class "Default")
      (node (ref "D5") (pin "A") (pinfunction "A_A") (pintype "passive"))
      (node (ref "D9") (pin "C") (pinfunction "C_C") (pintype "passive"))
      (node (ref "IC10") (pin "14") (pinfunction "OUT4_14") (pintype "output"))
      (node (ref "X5") (pin "4") (pinfunction "S_4") (pintype "passive"))
    )
    (net (code "45") (name "Net-(IC11A-O)") (class "Default")
      (node (ref "IC11") (pin "4") (pinfunction "O_4") (pintype "output"))
      (node (ref "R34") (pin "2") (pinfunction "2_2") (pintype "passive"))
    )
    (net (code "46") (name "Net-(IC13A-O)") (class "Default")
      (node (ref "IC13") (pin "4") (pinfunction "O_4") (pintype "output"))
      (node (ref "R36") (pin "2") (pinfunction "2_2") (pintype "passive"))
    )
    (net (code "47") (name "Net-(IC14-CNTDCDR)") (class "Default")
      (node (ref "IC14") (pin "16") (pinfunction "CNTDCDR_16") (pintype "bidirectional"))
      (node (ref "R44") (pin "2") (pinfunction "2_2") (pintype "passive"))
    )
    (net (code "48") (name "Net-(IC14-U{slash}~{D})") (class "Default")
      (node (ref "IC14") (pin "5") (pinfunction "U/~{D}_5") (pintype "bidirectional"))
      (node (ref "R45") (pin "2") (pinfunction "2_2") (pintype "passive"))
    )
    (net (code "49") (name "Net-(LED1-PadC)") (class "Default")
      (node (ref "LED1") (pin "C") (pinfunction "C_C") (pintype "passive"))
      (node (ref "R22") (pin "2") (pinfunction "2_2") (pintype "passive"))
    )
    (net (code "50") (name "Net-(LED7-PadA)") (class "Default")
      (node (ref "LED7") (pin "A") (pinfunction "A_A") (pintype "passive"))
      (node (ref "R44") (pin "1") (pinfunction "1_1") (pintype "passive"))
    )
    (net (code "51") (name "Net-(LED8-PadA)") (class "Default")
      (node (ref "LED8") (pin "A") (pinfunction "A_A") (pintype "passive"))
      (node (ref "R45") (pin "1") (pinfunction "1_1") (pintype "passive"))
    )
    (net (code "52") (name "Net-(LED10-PadC)") (class "Default")
      (node (ref "LED10") (pin "C") (pinfunction "C_C") (pintype "passive"))
      (node (ref "R32") (pin "2") (pinfunction "2_2") (pintype "passive"))
    )
    (net (code "53") (name "Net-(R4-Pad2)") (class "Default")
      (node (ref "R4") (pin "2") (pinfunction "2_2") (pintype "passive"))
      (node (ref "R6") (pin "1") (pinfunction "1_1") (pintype "passive"))
      (node (ref "X3") (pin "1") (pinfunction "1_1") (pintype "passive"))
    )
    (net (code "54") (name "Net-(R5-Pad2)") (class "Default")
      (node (ref "R5") (pin "2") (pinfunction "2_2") (pintype "passive"))
      (node (ref "R7") (pin "1") (pinfunction "1_1") (pintype "passive"))
      (node (ref "X4") (pin "1") (pinfunction "1_1") (pintype "passive"))
    )
    (net (code "55") (name "Net-(X1A-S)") (class "Default")
      (node (ref "R10") (pin "2") (pinfunction "2_2") (pintype "passive"))
      (node (ref "X1") (pin "1") (pinfunction "S_1") (pintype "passive"))
    )
    (net (code "56") (name "Net-(X1B-S)") (class "Default")
      (node (ref "C5") (pin "1") (pinfunction "1_1") (pintype "passive"))
      (node (ref "R9") (pin "2") (pinfunction "2_2") (pintype "passive"))
      (node (ref "X1") (pin "2") (pinfunction "S_2") (pintype "passive"))
    )
    (net (code "57") (name "Net-(X1C-S)") (class "Default")
      (node (ref "C6") (pin "1") (pinfunction "1_1") (pintype "passive"))
      (node (ref "R8") (pin "2") (pinfunction "2_2") (pintype "passive"))
      (node (ref "X1") (pin "3") (pinfunction "S_3") (pintype "passive"))
    )
    (net (code "58") (name "Net-(X6A-S)") (class "Default")
      (node (ref "R40") (pin "1") (pinfunction "1_1") (pintype "passive"))
      (node (ref "X6") (pin "1") (pinfunction "S_1") (pintype "passive"))
    )
    (net (code "59") (name "Net-(X6B-S)") (class "Default")
      (node (ref "R33") (pin "1") (pinfunction "1_1") (pintype "passive"))
      (node (ref "X6") (pin "2") (pinfunction "S_2") (pintype "passive"))
    )
    (net (code "60") (name "Net-(X8A-S)") (class "Default")
      (node (ref "R34") (pin "1") (pinfunction "1_1") (pintype "passive"))
      (node (ref "X8") (pin "1") (pinfunction "S_1") (pintype "passive"))
    )
    (net (code "61") (name "Net-(X8B-S)") (class "Default")
      (node (ref "R35") (pin "1") (pinfunction "1_1") (pintype "passive"))
      (node (ref "X8") (pin "2") (pinfunction "S_2") (pintype "passive"))
    )
    (net (code "62") (name "Net-(X10A-S)") (class "Default")
      (node (ref "R36") (pin "1") (pinfunction "1_1") (pintype "passive"))
      (node (ref "X10") (pin "1") (pinfunction "S_1") (pintype "passive"))
    )
    (net (code "63") (name "Net-(X10B-S)") (class "Default")
      (node (ref "R41") (pin "1") (pinfunction "1_1") (pintype "passive"))
      (node (ref "X10") (pin "2") (pinfunction "S_2") (pintype "passive"))
    )
    (net (code "64") (name "Net-(X11A-S)") (class "Default")
      (node (ref "R42") (pin "1") (pinfunction "1_1") (pintype "passive"))
      (node (ref "X11") (pin "1") (pinfunction "S_1") (pintype "passive"))
    )
    (net (code "65") (name "Net-(X11B-S)") (class "Default")
      (node (ref "R43") (pin "1") (pinfunction "1_1") (pintype "passive"))
      (node (ref "X11") (pin "2") (pinfunction "S_2") (pintype "passive"))
    )
    (net (code "66") (name "Net-(X12B-S)") (class "Default")
      (node (ref "R37") (pin "1") (pinfunction "1_1") (pintype "passive"))
      (node (ref "X12") (pin "2") (pinfunction "S_2") (pintype "passive"))
    )
    (net (code "67") (name "Net-(X12C-S)") (class "Default")
      (node (ref "R38") (pin "1") (pinfunction "1_1") (pintype "passive"))
      (node (ref "X12") (pin "3") (pinfunction "S_3") (pintype "passive"))
    )
    (net (code "68") (name "OSC") (class "Default")
      (node (ref "C1") (pin "1") (pinfunction "1_1") (pintype "passive"))
      (node (ref "IC5") (pin "16") (pinfunction "OSC_16") (pintype "bidirectional"))
      (node (ref "R12") (pin "1") (pinfunction "1_1") (pintype "passive"))
    )
    (net (code "69") (name "PGC(ICSPCLK)") (class "Default")
      (node (ref "IC12") (pin "16") (pinfunction "RB6/PGC/KBI2_16") (pintype "passive"))
      (node (ref "J1") (pin "5") (pinfunction "5_5") (pintype "passive"))
    )
    (net (code "70") (name "PGD(ICSPDAT)") (class "Default")
      (node (ref "IC12") (pin "17") (pinfunction "RB7/PGD/T3G/KBI3_17") (pintype "passive"))
      (node (ref "J1") (pin "4") (pinfunction "4_4") (pintype "passive"))
    )
    (net (code "71") (name "PGM(LVP)") (class "Default")
      (node (ref "J1") (pin "6") (pinfunction "6_6") (pintype "passive"))
    )
    (net (code "72") (name "QA") (class "Default")
      (node (ref "IC14") (pin "9") (pinfunction "CHA_9") (pintype "bidirectional"))
      (node (ref "X7") (pin "3") (pinfunction "S_3") (pintype "passive"))
    )
    (net (code "73") (name "QB") (class "Default")
      (node (ref "IC14") (pin "8") (pinfunction "CHB_8") (pintype "bidirectional"))
      (node (ref "X7") (pin "1") (pinfunction "S_1") (pintype "passive"))
    )
    (net (code "74") (name "RIGHT") (class "Default")
      (node (ref "IC12") (pin "10") (pinfunction "RB2/CANTX/CTED1/INT2_10") (pintype "passive"))
      (node (ref "R35") (pin "2") (pinfunction "2_2") (pintype "passive"))
    )
    (net (code "75") (name "RX") (class "Default")
      (node (ref "IC12") (pin "1") (pinfunction "RC7/CANRX/RX1/DT1/CCP4_1") (pintype "passive"))
      (node (ref "IC3") (pin "1") (pinfunction "TXD_1") (pintype "output"))
    )
    (net (code "76") (name "SEN_1") (class "Default")
      (node (ref "IC10") (pin "1") (pinfunction "SEN_A_1") (pintype "input"))
      (node (ref "R14") (pin "1") (pinfunction "1_1") (pintype "passive"))
      (node (ref "R25") (pin "1") (pinfunction "1_1") (pintype "passive"))
    )
    (net (code "77") (name "SEN_2") (class "Default")
      (node (ref "IC10") (pin "15") (pinfunction "SEN_B_15") (pintype "input"))
      (node (ref "R15") (pin "1") (pinfunction "1_1") (pintype "passive"))
      (node (ref "R26") (pin "1") (pinfunction "1_1") (pintype "passive"))
    )
    (net (code "78") (name "SQW{slash}~{INT}") (class "Default")
      (node (ref "IC12") (pin "15") (pinfunction "RB5/TOCKI/T3CKI/CCP5/KBI1_15") (pintype "passive"))
      (node (ref "IC6") (pin "3") (pinfunction "SQW/~{INT}_3") (pintype "bidirectional"))
      (node (ref "R30") (pin "2") (pinfunction "2_2") (pintype "passive"))
    )
    (net (code "79") (name "STEP") (class "Default")
      (node (ref "IC12") (pin "25") (pinfunction "RE0/AN5/*RD_25") (pintype "passive"))
      (node (ref "IC5") (pin "18") (pinfunction "CLOCK_18") (pintype "input"))
    )
    (net (code "80") (name "TRIG") (class "Default")
      (node (ref "IC12") (pin "24") (pinfunction "RA5/AN4//HLVDIN/T1CKI/*SS_24") (pintype "passive"))
      (node (ref "R7") (pin "2") (pinfunction "2_2") (pintype "passive"))
    )
    (net (code "81") (name "TX") (class "Default")
      (node (ref "IC12") (pin "44") (pinfunction "RC6/CANTX/TX1/CK1/CCP3_44") (pintype "passive"))
      (node (ref "IC3") (pin "4") (pinfunction "RXD_4") (pintype "input"))
    )
    (net (code "82") (name "UP{slash}MENU") (class "Default")
      (node (ref "IC12") (pin "8") (pinfunction "RB0/AN10/FLT0/INT0_8") (pintype "passive"))
      (node (ref "R43") (pin "2") (pinfunction "2_2") (pintype "passive"))
    )
    (net (code "83") (name "VPP{slash}~{MCLR}") (class "Default")
      (node (ref "IC12") (pin "18") (pinfunction "*MCLR/RE3_18") (pintype "passive"))
      (node (ref "J1") (pin "1") (pinfunction "1_1") (pintype "passive"))
    )
    (net (code "84") (name "VREF") (class "Default")
      (node (ref "C8") (pin "1") (pinfunction "1_1") (pintype "passive"))
      (node (ref "IC5") (pin "15") (pinfunction "VREF_15") (pintype "input"))
      (node (ref "R18") (pin "1") (pinfunction "1_1") (pintype "passive"))
      (node (ref "R19") (pin "2") (pinfunction "2_2") (pintype "passive"))
    )
    (net (code "85") (name "unconnected-(IC3-CBUS1-Pad14)") (class "Default")
      (node (ref "IC3") (pin "14") (pinfunction "CBUS1_14") (pintype "bidirectional"))
    )
    (net (code "86") (name "unconnected-(IC3-CBUS2-Pad7)") (class "Default")
      (node (ref "IC3") (pin "7") (pinfunction "CBUS2_7") (pintype "bidirectional"))
    )
    (net (code "87") (name "unconnected-(IC3-CBUS3-Pad16)") (class "Default")
      (node (ref "IC3") (pin "16") (pinfunction "CBUS3_16") (pintype "bidirectional"))
    )
    (net (code "88") (name "unconnected-(IC3-~{CTS}-Pad6)") (class "Default")
      (node (ref "IC3") (pin "6") (pinfunction "~{CTS}_6") (pintype "input"))
    )
    (net (code "89") (name "unconnected-(IC3-~{RTS}-Pad2)") (class "Default")
      (node (ref "IC3") (pin "2") (pinfunction "~{RTS}_2") (pintype "output"))
    )
    (net (code "90") (name "unconnected-(IC5-SYNC-Pad1)") (class "Default")
      (node (ref "IC5") (pin "1") (pinfunction "SYNC_1") (pintype "output"))
    )
    (net (code "91") (name "unconnected-(IC6-~{RST}-Pad4)") (class "Default")
      (node (ref "IC6") (pin "4") (pinfunction "~{RST}_4") (pintype "bidirectional"))
    )
    (net (code "92") (name "unconnected-(IC12-NC-Pad34)") (class "Default")
      (node (ref "IC12") (pin "34") (pinfunction "NC_34") (pintype "passive"))
    )
    (net (code "93") (name "unconnected-(IC12-NC_2-Pad12)") (class "Default")
      (node (ref "IC12") (pin "12") (pinfunction "NC_2_12") (pintype "passive"))
    )
    (net (code "94") (name "unconnected-(IC12-NC_3-Pad13)") (class "Default")
      (node (ref "IC12") (pin "13") (pinfunction "NC_3_13") (pintype "passive"))
    )
    (net (code "95") (name "unconnected-(IC12-NC_4-Pad33)") (class "Default")
      (node (ref "IC12") (pin "33") (pinfunction "NC_4_33") (pintype "passive"))
    )
    (net (code "96") (name "unconnected-(IC12-OSC2{slash}CLKO{slash}RA6-Pad31)") (class "Default")
      (node (ref "IC12") (pin "31") (pinfunction "OSC2/CLKO/RA6_31") (pintype "passive"))
    )
    (net (code "97") (name "unconnected-(IC12-RC5{slash}SDO-Pad43)") (class "Default")
      (node (ref "IC12") (pin "43") (pinfunction "RC5/SDO_43") (pintype "passive"))
    )
    (net (code "98") (name "unconnected-(IC14-CNTCAS-Pad15)") (class "Default")
      (node (ref "IC14") (pin "15") (pinfunction "CNTCAS_15") (pintype "bidirectional"))
    )
    (net (code "99") (name "unconnected-(U$1-PadP$1)") (class "Default")
      (node (ref "U$1") (pin "P$1") (pinfunction "P$1_P$1") (pintype "bidirectional"))
    )
    (net (code "100") (name "unconnected-(U$2-PadP$1)") (class "Default")
      (node (ref "U$2") (pin "P$1") (pinfunction "P$1_P$1") (pintype "bidirectional"))
    )
    (net (code "101") (name "unconnected-(U$3-PadP$1)") (class "Default")
      (node (ref "U$3") (pin "P$1") (pinfunction "P$1_P$1") (pintype "bidirectional"))
    )
    (net (code "102") (name "unconnected-(U$4-PadP$1)") (class "Default")
      (node (ref "U$4") (pin "P$1") (pinfunction "P$1_P$1") (pintype "bidirectional"))
    )
    (net (code "103") (name "unconnected-(X1E-S-Pad5)") (class "Default")
      (node (ref "X1") (pin "5") (pinfunction "S_5") (pintype "passive"))
    )
    (net (code "104") (name "~{INH1}") (class "Default")
      (node (ref "IC10") (pin "6") (pinfunction "ENABLE_A_6") (pintype "input"))
      (node (ref "IC5") (pin "5") (pinfunction "INH1_5") (pintype "output"))
    )
    (net (code "105") (name "~{INH2}") (class "Default")
      (node (ref "IC10") (pin "11") (pinfunction "ENABLE_B_11") (pintype "input"))
      (node (ref "IC5") (pin "8") (pinfunction "INH2_8") (pintype "output"))
    )
    (net (code "106") (name "~{READ_COUNTER}") (class "Default")
      (node (ref "IC12") (pin "19") (pinfunction "RA0/CVREF/AN0/ULPWU_19") (pintype "passive"))
      (node (ref "IC14") (pin "4") (pinfunction "~{OE}_4") (pintype "bidirectional"))
    )
    (net (code "107") (name "~{RESET_COUNTER}") (class "Default")
      (node (ref "IC12") (pin "20") (pinfunction "RA1/AN1/C1INC_20") (pintype "passive"))
      (node (ref "IC14") (pin "7") (pinfunction "~{RST}_7") (pintype "bidirectional"))
    )
    (net (code "108") (name "~{RESET_DRIVE}") (class "Default")
      (node (ref "IC12") (pin "32") (pinfunction "RC0/SOSCO/SLCKI_32") (pintype "passive"))
      (node (ref "IC5") (pin "20") (pinfunction "RESET_20") (pintype "input"))
    )
  )
)
